# UltraSonic_Anemometer_HW.net
KiCad netlist of a schematic drawn in EasyEDA Pro
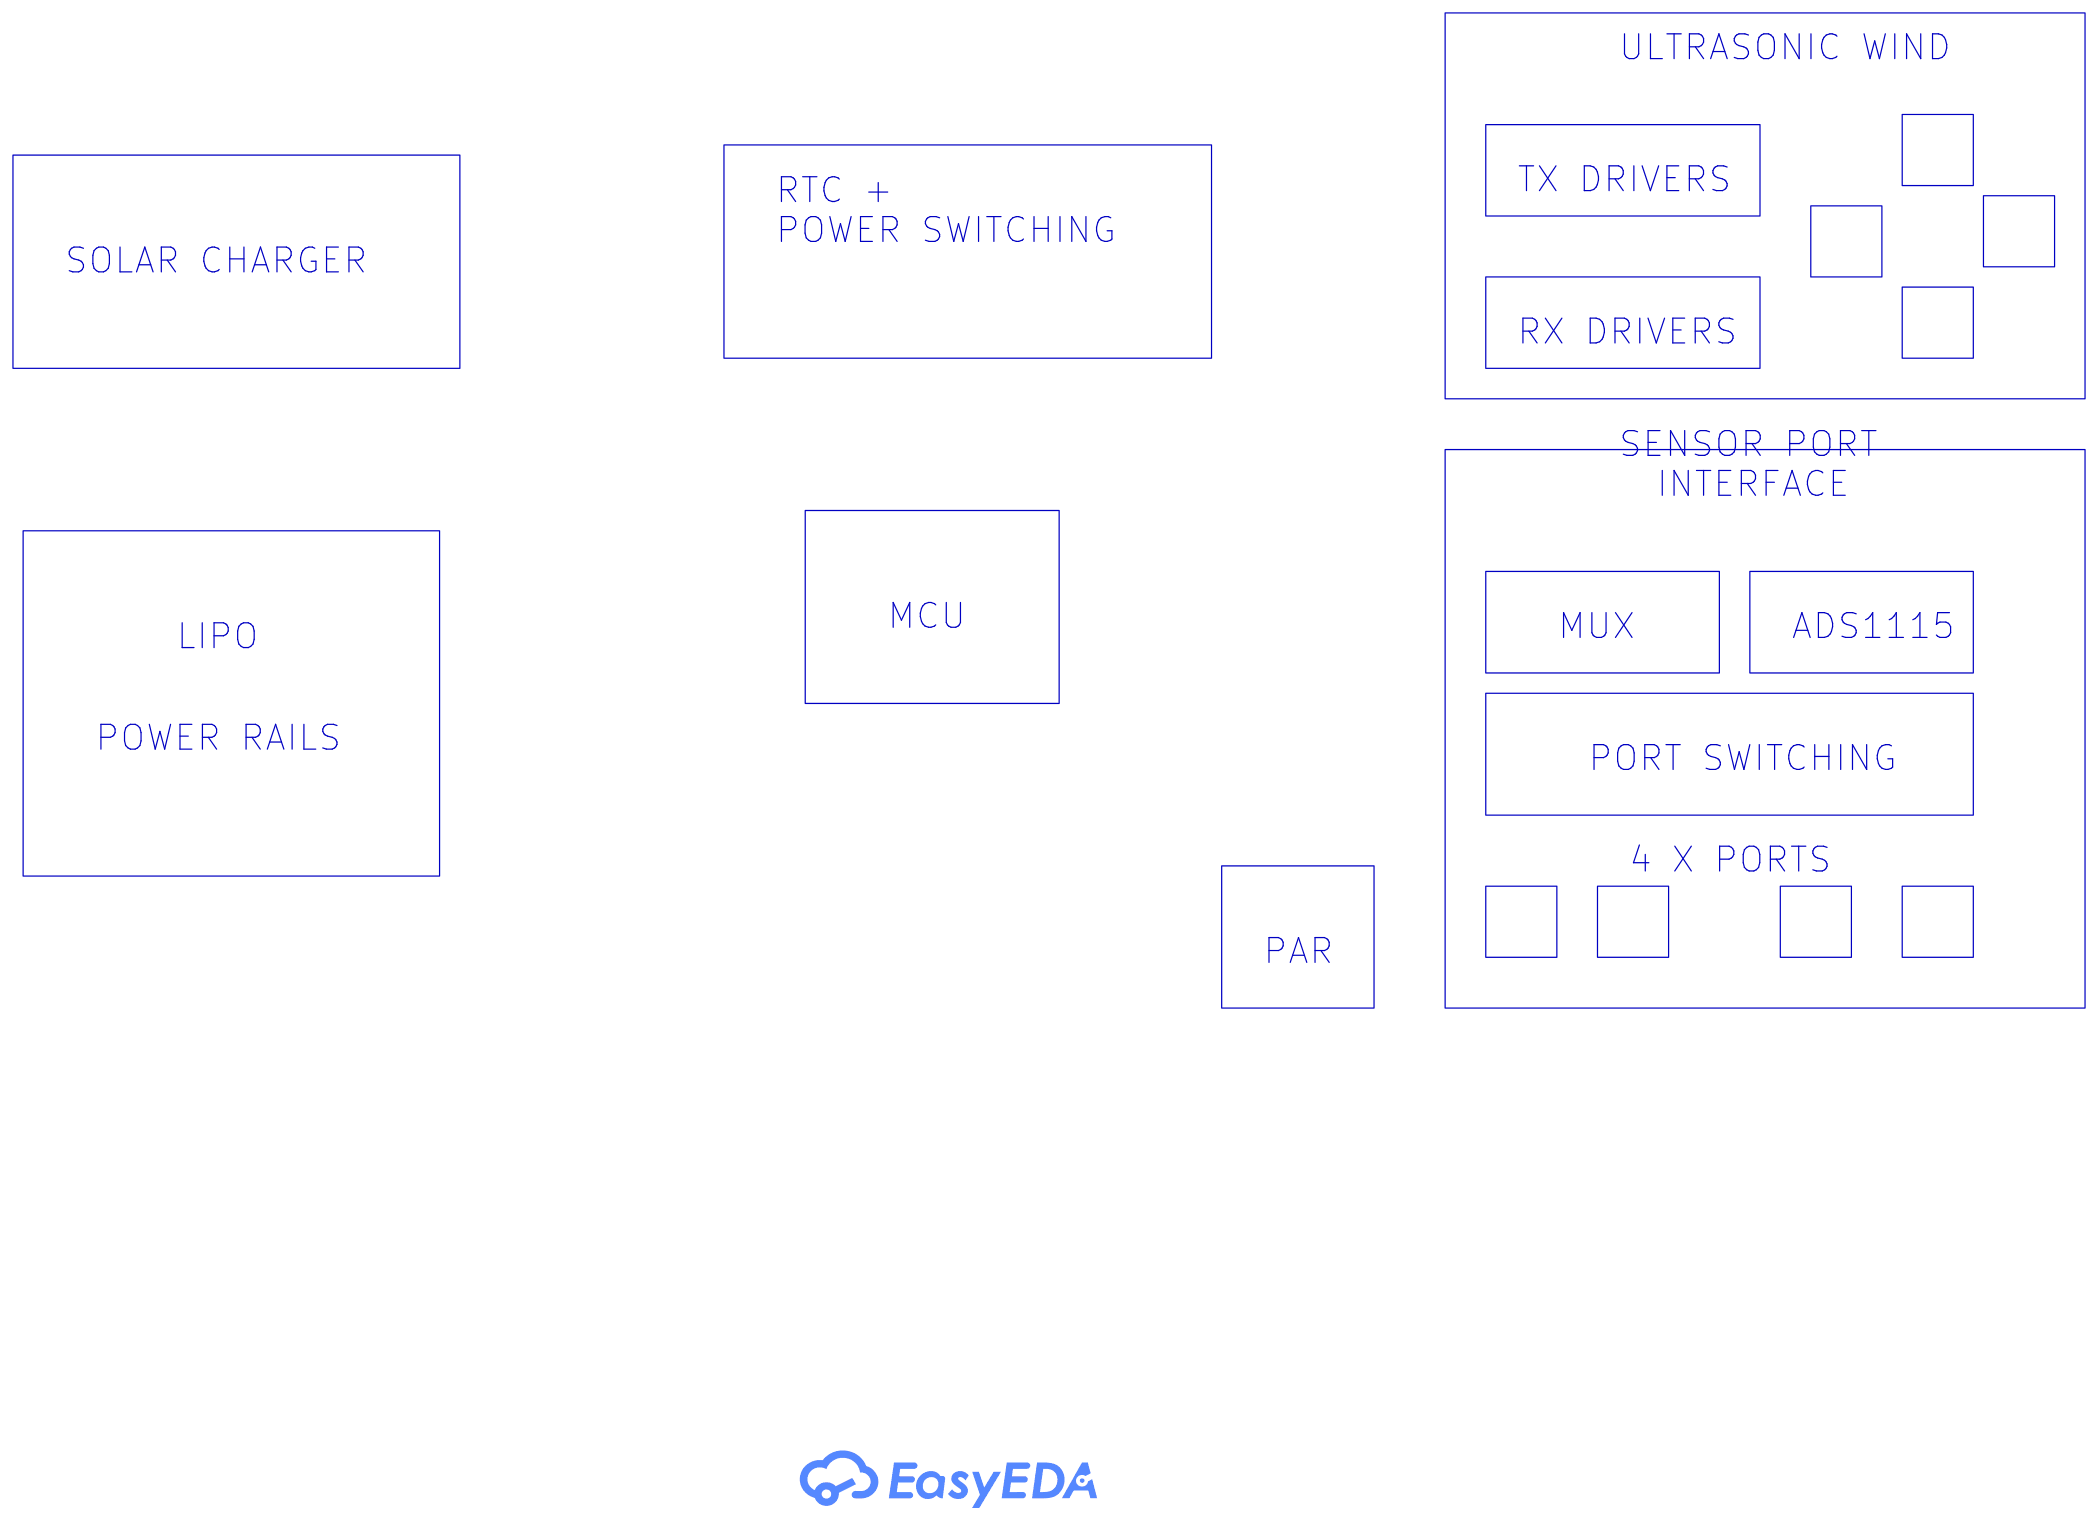
[diagram p0: TOP_LEVEL]
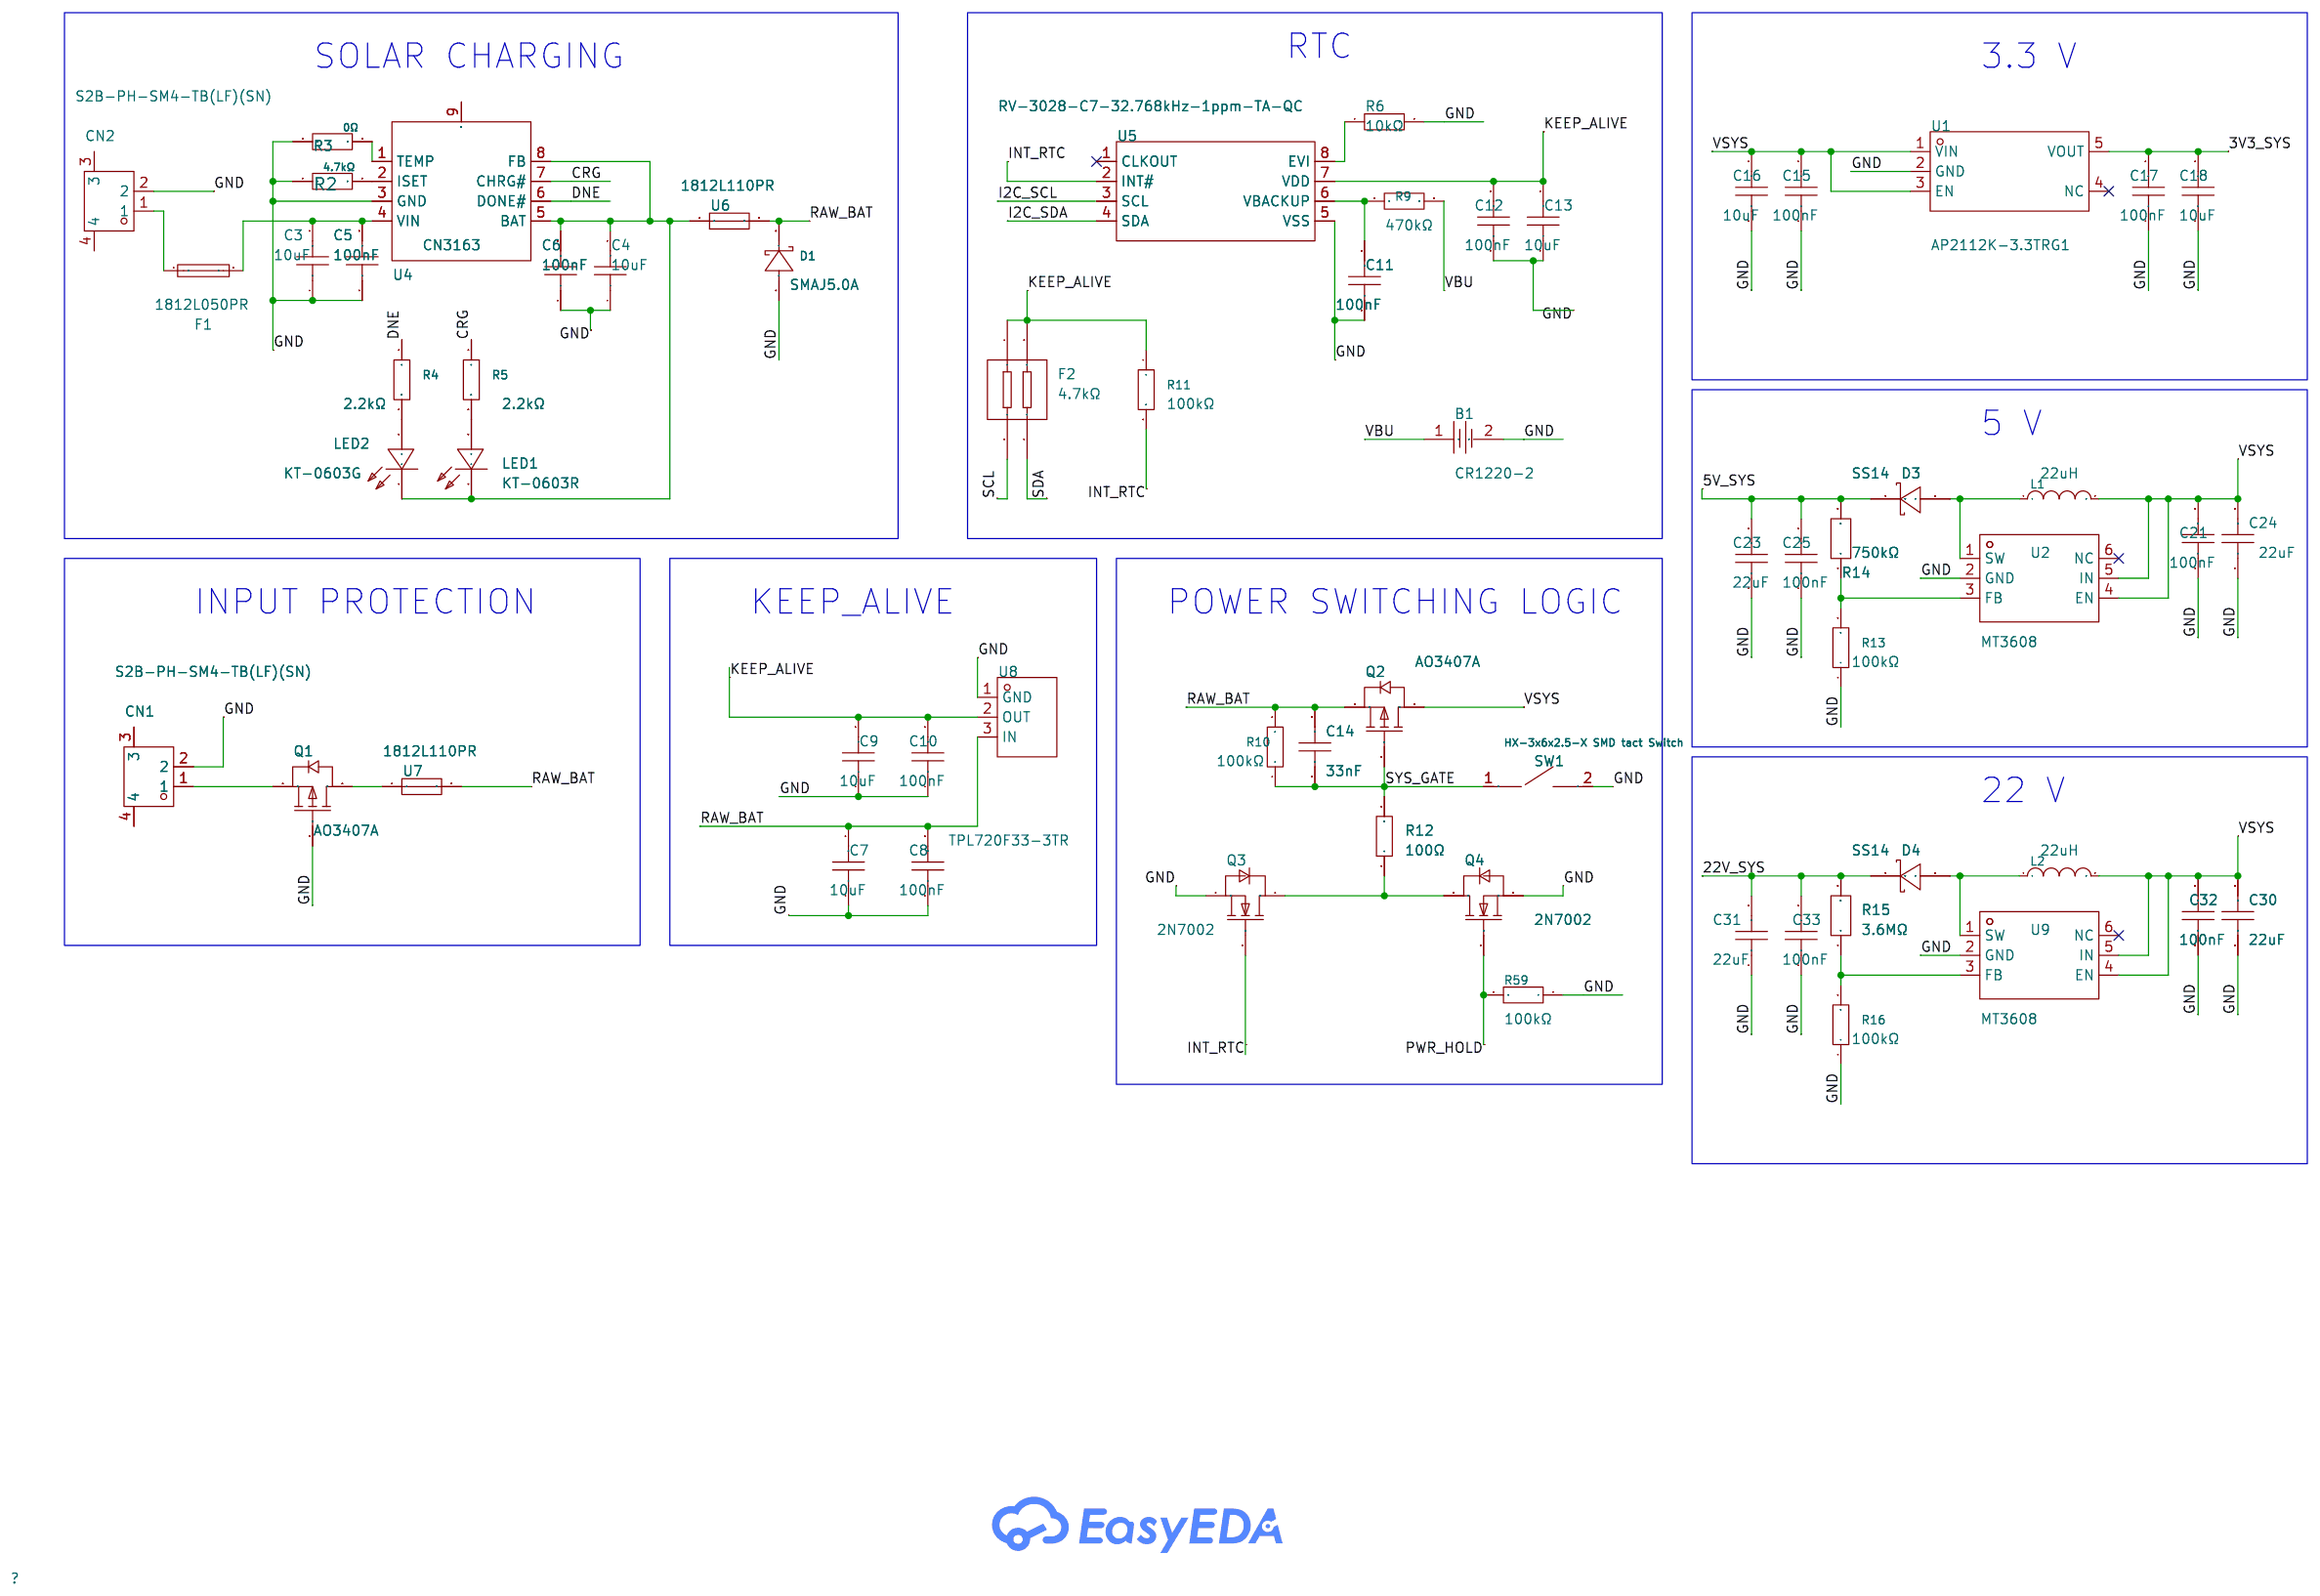
[diagram p1: POWER]
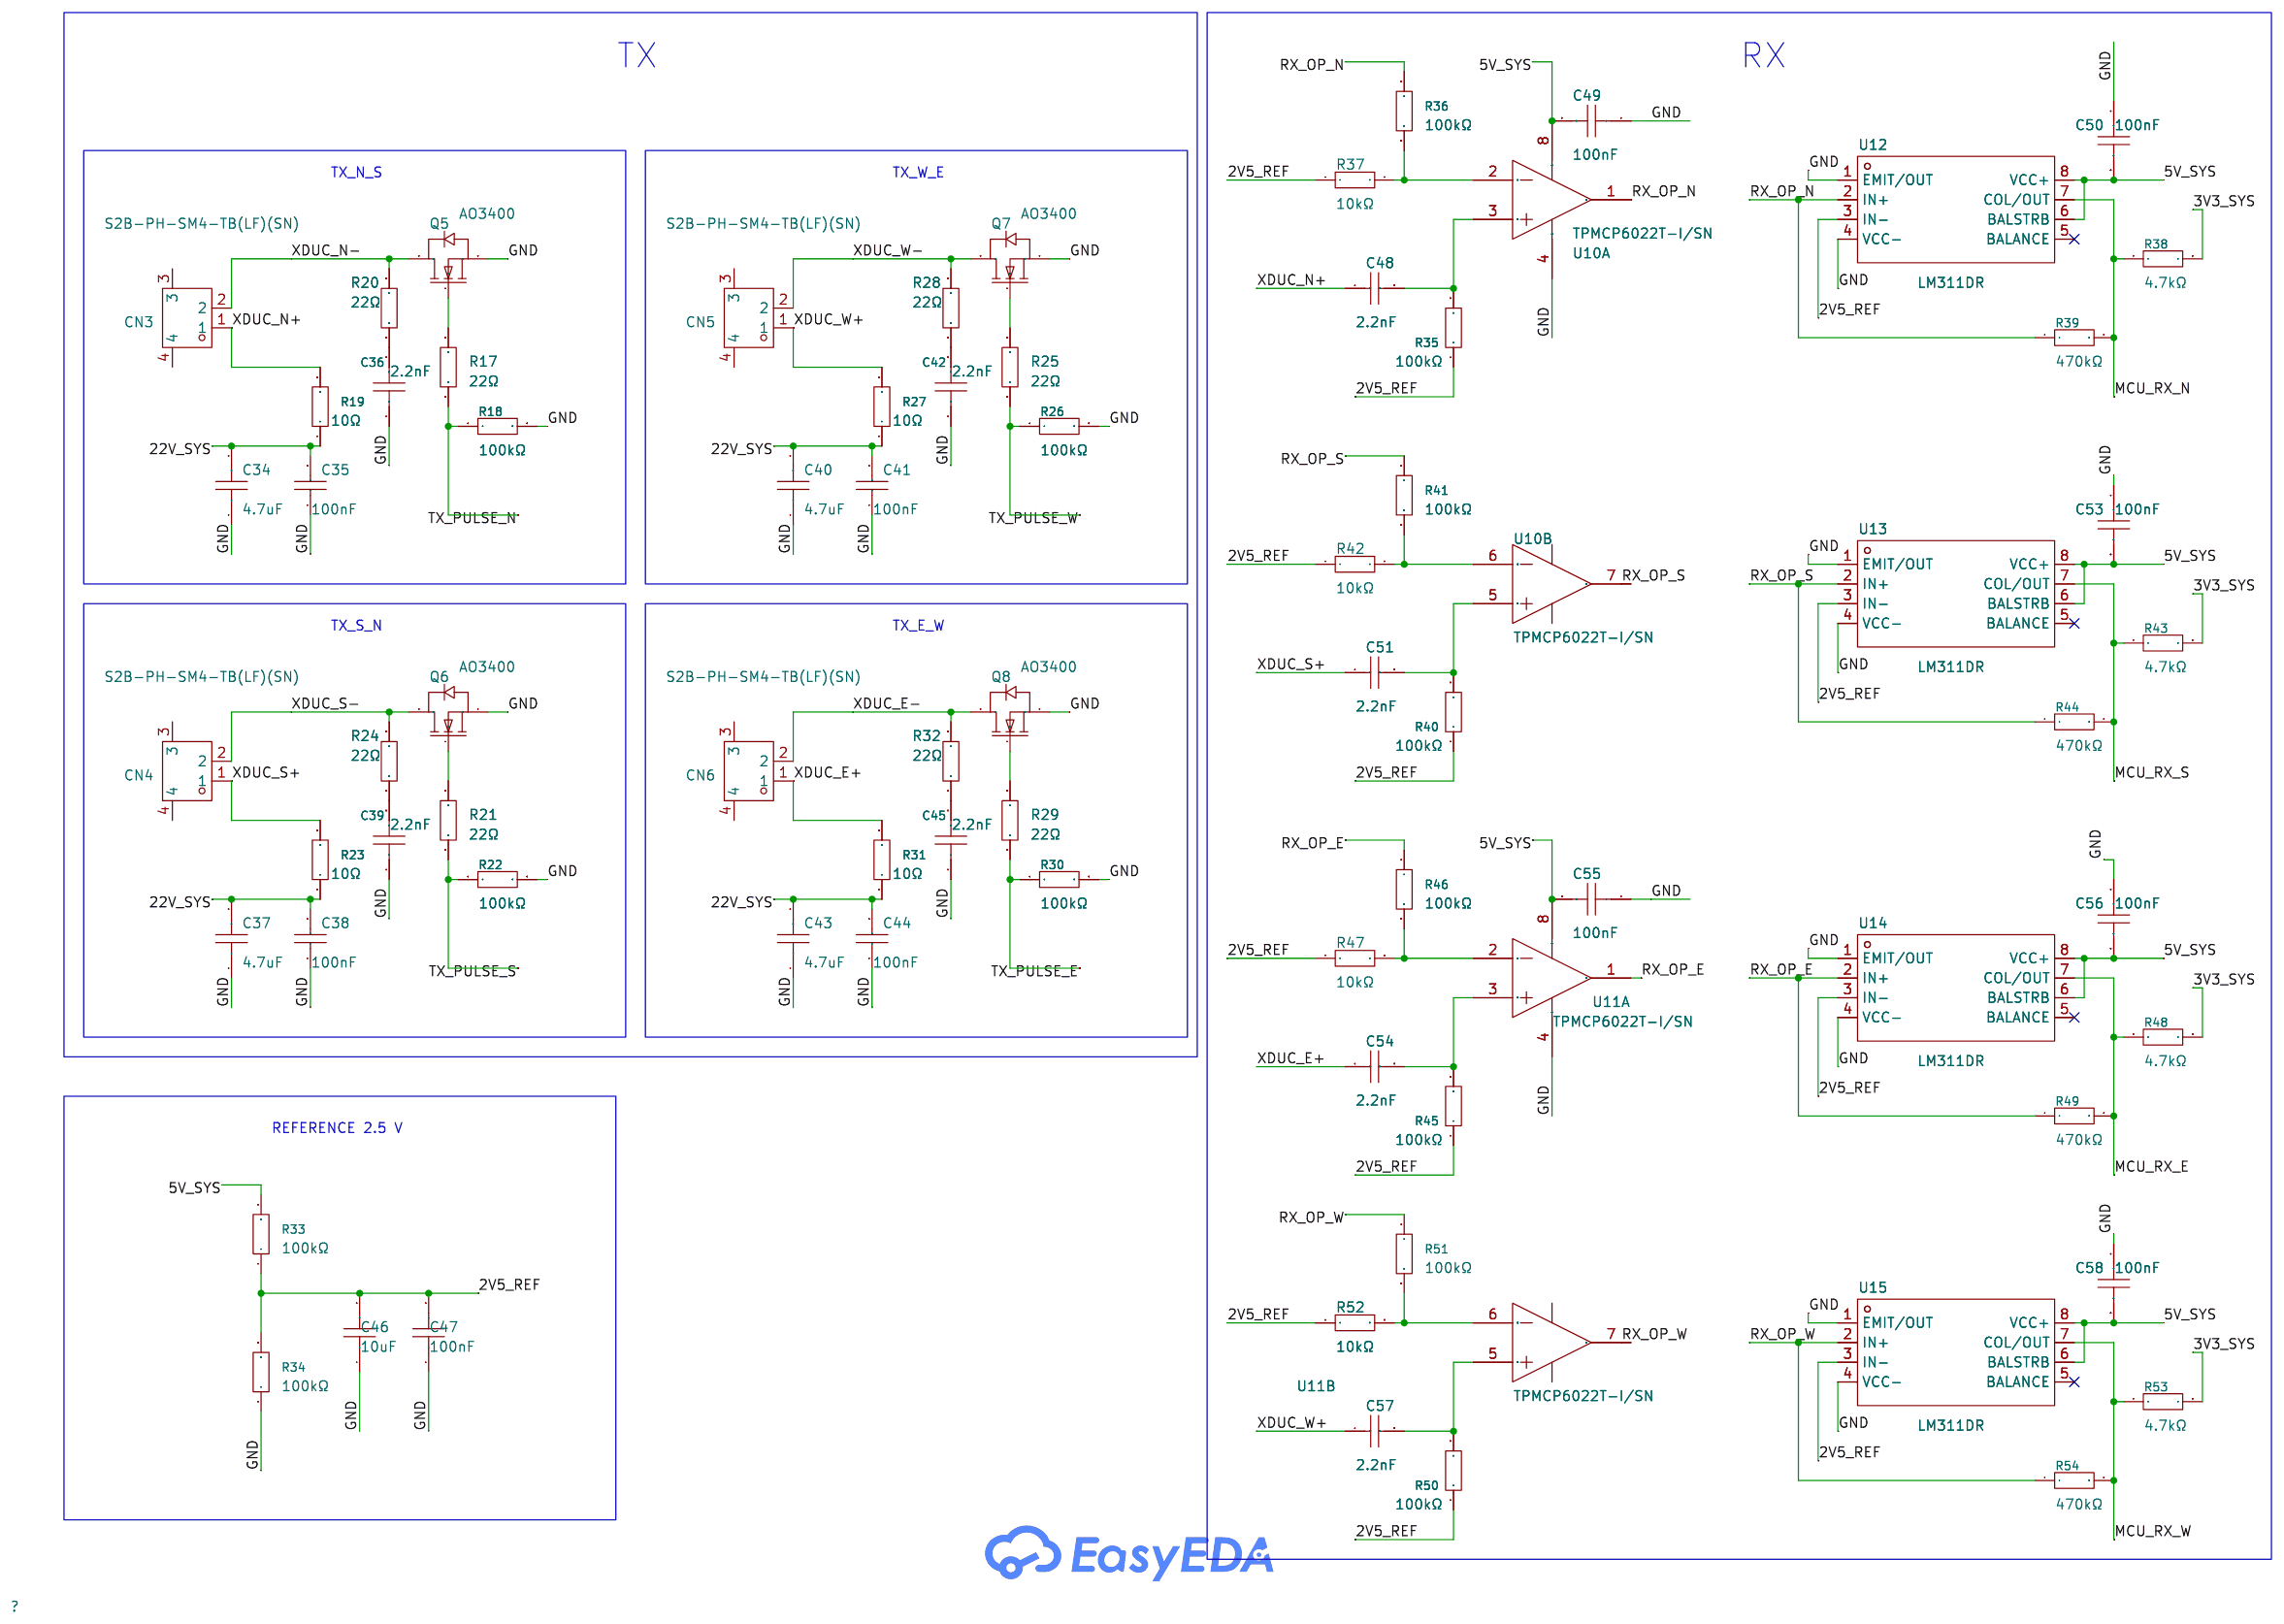
[diagram p2: UlTRASONIC]
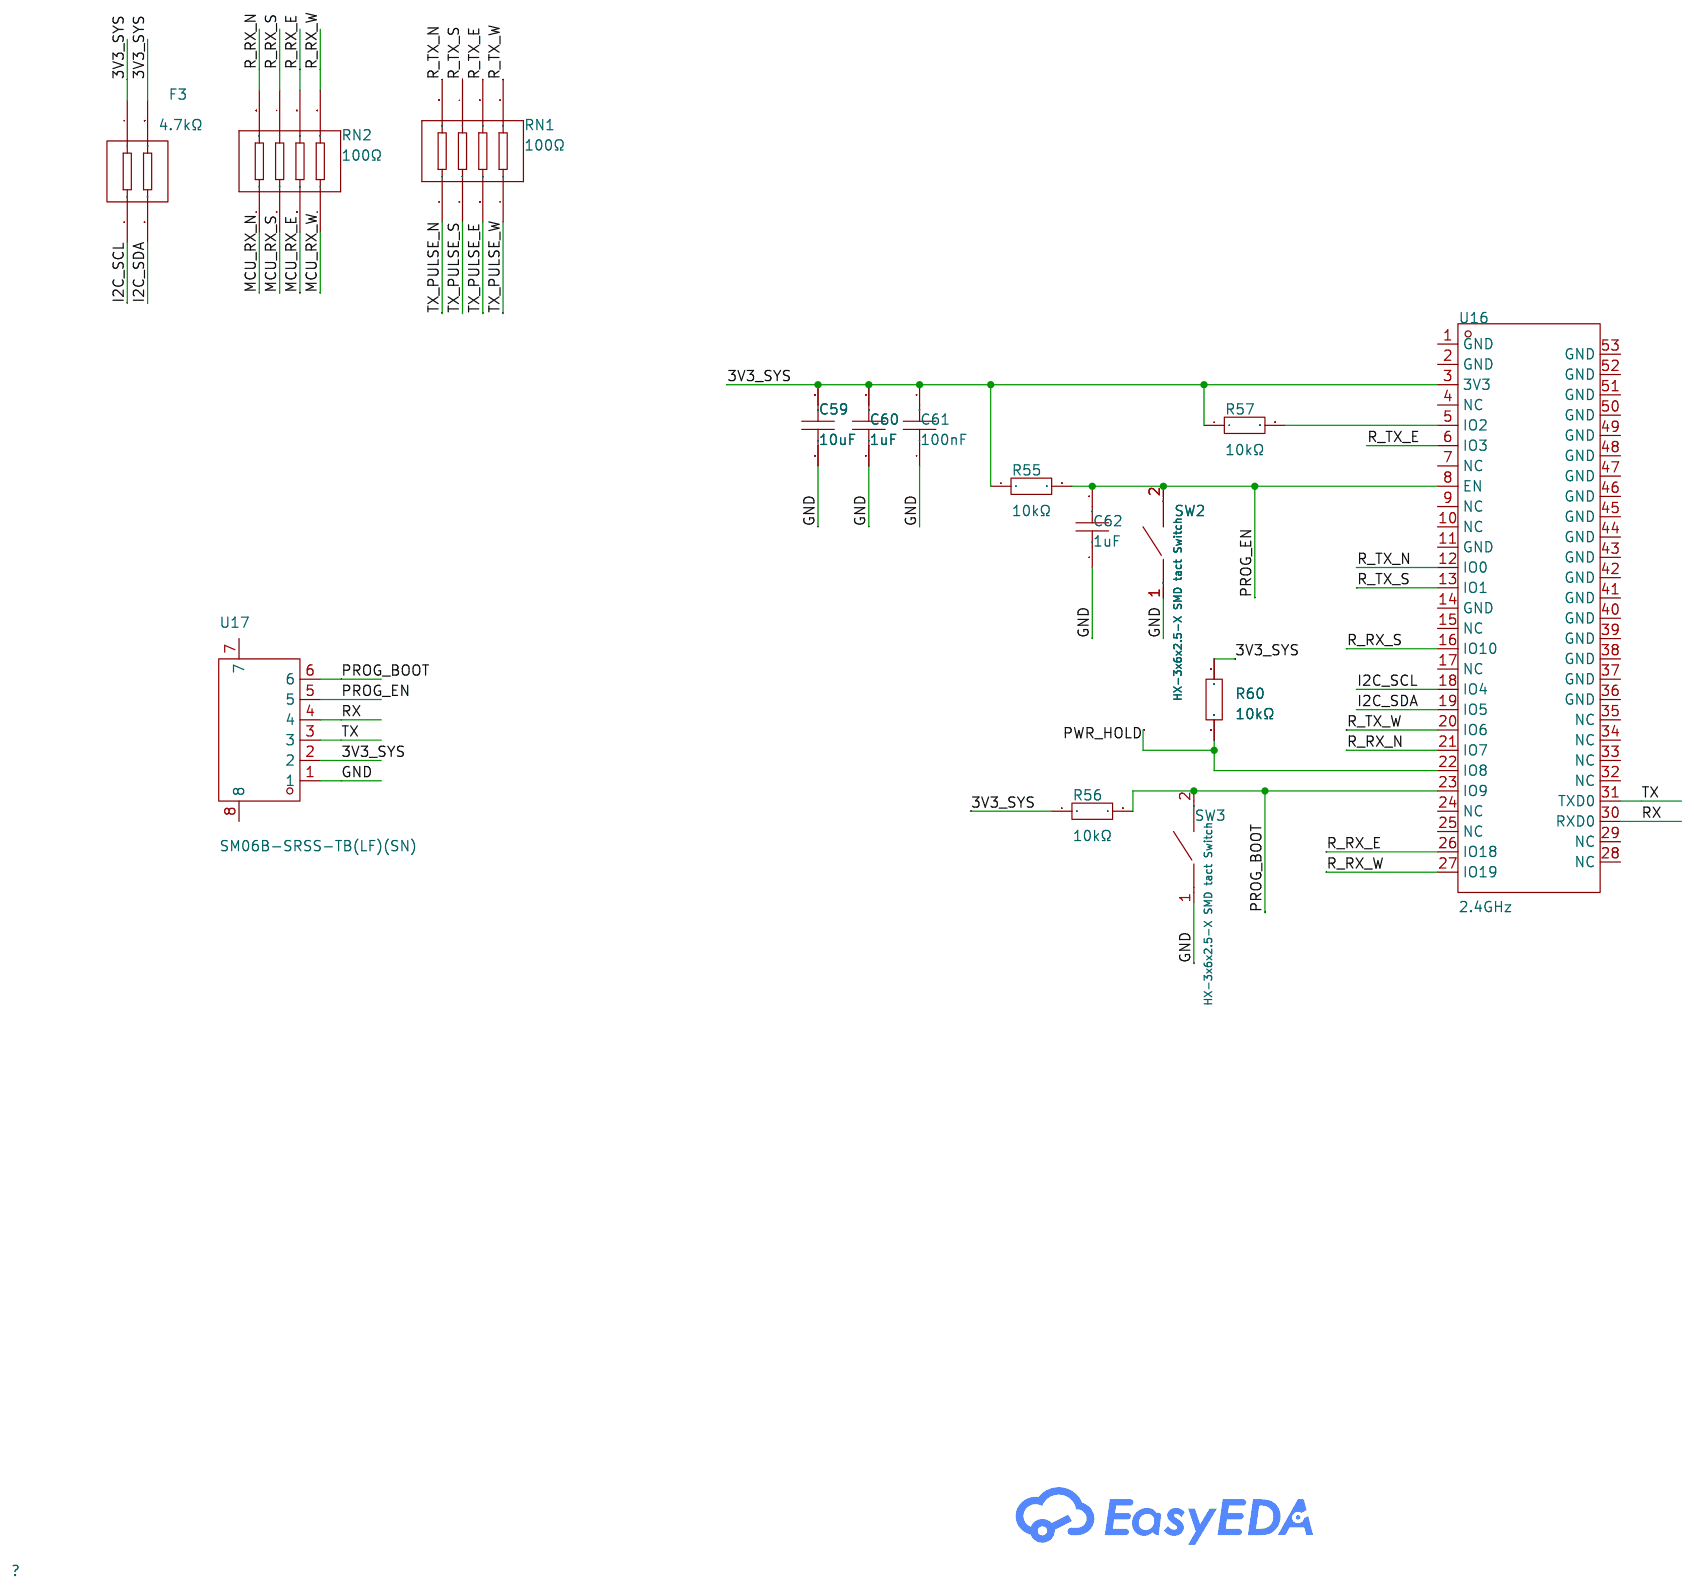
[diagram p3: MCU]
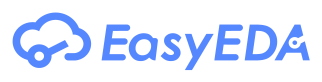
[diagram p4: SENSOR PORTS]

(export (version "E")
  (design (tool "Eeschema 10.0.6"))
  (components
    (comp (ref "B1")
      (value "CR1220-2")
      (footprint "easyedapro:BAT-SMD_CR1220-2")
      (description "Connector Type:Battery Holder Battery Type:CR1220 Operating Temperature:- Operating Temperature:-")
      (fields (field (name "Manufacturer") "QIJEY"))
      (libsource (lib "easyedapro") (part "CR1220-2"))
    )
    (comp (ref "C3")
      (value "10uF")
      (footprint "easyedapro:C0603")
      (fields
        (field (name "Manufacturer Part") "GRM188Z71A106KA73D")
        (field (name "Manufacturer") "muRata(村田)")
      )
      (libsource (lib "easyedapro") (part "GRM188Z71A106KA73D"))
    )
    (comp (ref "C4")
      (value "10uF")
      (footprint "easyedapro:C0603")
      (fields
        (field (name "Manufacturer Part") "GRM188Z71A106KA73D")
        (field (name "Manufacturer") "muRata(村田)")
      )
      (libsource (lib "easyedapro") (part "GRM188Z71A106KA73D"))
    )
    (comp (ref "C5")
      (value "100nF")
      (footprint "easyedapro:C0402")
      (description "Capacitance:100nF Tolerance:±10% Tolerance:±10% Voltage Rating:16V Temperature Coefficient:X7R")
      (fields
        (field (name "Manufacturer Part") "CL05B104KO5NNNC")
        (field (name "Manufacturer") "SAMSUNG(三星)")
      )
      (libsource (lib "easyedapro") (part "CL05B104KO5NNNC"))
    )
    (comp (ref "C6")
      (value "100nF")
      (footprint "easyedapro:C0402")
      (description "Capacitance:100nF Tolerance:±10% Tolerance:±10% Voltage Rating:16V Temperature Coefficient:X7R")
      (fields
        (field (name "Manufacturer Part") "CL05B104KO5NNNC")
        (field (name "Manufacturer") "SAMSUNG(三星)")
      )
      (libsource (lib "easyedapro") (part "CL05B104KO5NNNC"))
    )
    (comp (ref "C7")
      (value "10uF")
      (footprint "easyedapro:C0603")
      (fields
        (field (name "Manufacturer Part") "GRM188Z71A106KA73D")
        (field (name "Manufacturer") "muRata(村田)")
      )
      (libsource (lib "easyedapro") (part "GRM188Z71A106KA73D"))
    )
    (comp (ref "C8")
      (value "100nF")
      (footprint "easyedapro:C0402")
      (description "Capacitance:100nF Tolerance:±10% Tolerance:±10% Voltage Rating:16V Temperature Coefficient:X7R")
      (fields
        (field (name "Manufacturer Part") "CL05B104KO5NNNC")
        (field (name "Manufacturer") "SAMSUNG(三星)")
      )
      (libsource (lib "easyedapro") (part "CL05B104KO5NNNC"))
    )
    (comp (ref "C9")
      (value "10uF")
      (footprint "easyedapro:C0603")
      (fields
        (field (name "Manufacturer Part") "GRM188Z71A106KA73D")
        (field (name "Manufacturer") "muRata(村田)")
      )
      (libsource (lib "easyedapro") (part "GRM188Z71A106KA73D"))
    )
    (comp (ref "C10")
      (value "100nF")
      (footprint "easyedapro:C0402")
      (description "Capacitance:100nF Tolerance:±10% Tolerance:±10% Voltage Rating:16V Temperature Coefficient:X7R")
      (fields
        (field (name "Manufacturer Part") "CL05B104KO5NNNC")
        (field (name "Manufacturer") "SAMSUNG(三星)")
      )
      (libsource (lib "easyedapro") (part "CL05B104KO5NNNC"))
    )
    (comp (ref "C11")
      (value "100nF")
      (footprint "easyedapro:C0402")
      (description "Capacitance:100nF Tolerance:±10% Tolerance:±10% Voltage Rating:16V Temperature Coefficient:X7R")
      (fields
        (field (name "Manufacturer Part") "CL05B104KO5NNNC")
        (field (name "Manufacturer") "SAMSUNG(三星)")
      )
      (libsource (lib "easyedapro") (part "CL05B104KO5NNNC"))
    )
    (comp (ref "C12")
      (value "100nF")
      (footprint "easyedapro:C0402")
      (description "Capacitance:100nF Tolerance:±10% Tolerance:±10% Voltage Rating:16V Temperature Coefficient:X7R")
      (fields
        (field (name "Manufacturer Part") "CL05B104KO5NNNC")
        (field (name "Manufacturer") "SAMSUNG(三星)")
      )
      (libsource (lib "easyedapro") (part "CL05B104KO5NNNC"))
    )
    (comp (ref "C13")
      (value "10uF")
      (footprint "easyedapro:C0603")
      (fields
        (field (name "Manufacturer Part") "GRM188Z71A106KA73D")
        (field (name "Manufacturer") "muRata(村田)")
      )
      (libsource (lib "easyedapro") (part "GRM188Z71A106KA73D"))
    )
    (comp (ref "C14")
      (value "33nF")
      (footprint "easyedapro:C0402")
      (description "Capacitance:33nF Tolerance:±10% Tolerance:±10% Voltage Rating:16V Temperature Coefficient:X7R")
      (fields (field (name "Manufacturer Part") "0402B333K160CT") (field (name "Manufacturer") "Walsin(华新科)"))
      (libsource (lib "easyedapro") (part "0402B333K160CT"))
    )
    (comp (ref "C15")
      (value "100nF")
      (footprint "easyedapro:C0402")
      (description "Capacitance:100nF Tolerance:±10% Tolerance:±10% Voltage Rating:16V Temperature Coefficient:X7R")
      (fields
        (field (name "Manufacturer Part") "CL05B104KO5NNNC")
        (field (name "Manufacturer") "SAMSUNG(三星)")
      )
      (libsource (lib "easyedapro") (part "CL05B104KO5NNNC"))
    )
    (comp (ref "C16")
      (value "10uF")
      (footprint "easyedapro:C0603")
      (fields
        (field (name "Manufacturer Part") "GRM188Z71A106KA73D")
        (field (name "Manufacturer") "muRata(村田)")
      )
      (libsource (lib "easyedapro") (part "GRM188Z71A106KA73D"))
    )
    (comp (ref "C17")
      (value "100nF")
      (footprint "easyedapro:C0402")
      (description "Capacitance:100nF Tolerance:±10% Tolerance:±10% Voltage Rating:16V Temperature Coefficient:X7R")
      (fields
        (field (name "Manufacturer Part") "CL05B104KO5NNNC")
        (field (name "Manufacturer") "SAMSUNG(三星)")
      )
      (libsource (lib "easyedapro") (part "CL05B104KO5NNNC"))
    )
    (comp (ref "C18")
      (value "10uF")
      (footprint "easyedapro:C0603")
      (fields
        (field (name "Manufacturer Part") "GRM188Z71A106KA73D")
        (field (name "Manufacturer") "muRata(村田)")
      )
      (libsource (lib "easyedapro") (part "GRM188Z71A106KA73D"))
    )
    (comp (ref "C21")
      (value "100nF")
      (footprint "easyedapro:C0402")
      (description "Capacitance:100nF Tolerance:±10% Tolerance:±10% Voltage Rating:16V Temperature Coefficient:X7R")
      (fields
        (field (name "Manufacturer Part") "CL05B104KO5NNNC")
        (field (name "Manufacturer") "SAMSUNG(三星)")
      )
      (libsource (lib "easyedapro") (part "CL05B104KO5NNNC"))
    )
    (comp (ref "C23")
      (value "22uF")
      (footprint "easyedapro:C0603")
      (description "Capacitance:22uF Tolerance:±20% Tolerance:±20% Voltage Rating:10V Temperature Coefficient:X5R")
      (fields
        (field (name "Manufacturer Part") "CL10A226MP8NUNE")
        (field (name "Manufacturer") "SAMSUNG(三星)")
      )
      (libsource (lib "easyedapro") (part "CL10A226MP8NUNE"))
    )
    (comp (ref "C24")
      (value "22uF")
      (footprint "easyedapro:C0603")
      (description "Capacitance:22uF Tolerance:±20% Tolerance:±20% Voltage Rating:10V Temperature Coefficient:X5R")
      (fields
        (field (name "Manufacturer Part") "CL10A226MP8NUNE")
        (field (name "Manufacturer") "SAMSUNG(三星)")
      )
      (libsource (lib "easyedapro") (part "CL10A226MP8NUNE"))
    )
    (comp (ref "C25")
      (value "100nF")
      (footprint "easyedapro:C0402")
      (description "Capacitance:100nF Tolerance:±10% Tolerance:±10% Voltage Rating:16V Temperature Coefficient:X7R")
      (fields
        (field (name "Manufacturer Part") "CL05B104KO5NNNC")
        (field (name "Manufacturer") "SAMSUNG(三星)")
      )
      (libsource (lib "easyedapro") (part "CL05B104KO5NNNC"))
    )
    (comp (ref "C30")
      (value "22uF")
      (footprint "easyedapro:C1210")
      (description "Capacitance:22uF Tolerance:±10% Tolerance:±10% Voltage Rating:25V Temperature Coefficient:X7R")
      (fields
        (field (name "Manufacturer Part") "CL32B226KAJNNNE")
        (field (name "Manufacturer") "SAMSUNG(三星)")
      )
      (libsource (lib "easyedapro") (part "CL32B226KAJNNNE"))
    )
    (comp (ref "C31")
      (value "22uF")
      (footprint "easyedapro:C1210")
      (description "Capacitance:22uF Tolerance:±10% Tolerance:±10% Voltage Rating:25V Temperature Coefficient:X7R")
      (fields
        (field (name "Manufacturer Part") "CL32B226KAJNNNE")
        (field (name "Manufacturer") "SAMSUNG(三星)")
      )
      (libsource (lib "easyedapro") (part "CL32B226KAJNNNE"))
    )
    (comp (ref "C32")
      (value "100nF")
      (footprint "easyedapro:C0402")
      (description "Capacitance:100nF Tolerance:±10% Tolerance:±10% Voltage Rating:25V Temperature Coefficient:X7R")
      (fields
        (field (name "Manufacturer Part") "CGA0402X7R104K250GT")
        (field (name "Manufacturer") "HRE(芯声)")
      )
      (libsource (lib "easyedapro") (part "CGA0402X7R104K250GT"))
    )
    (comp (ref "C33")
      (value "100nF")
      (footprint "easyedapro:C0402")
      (description "Capacitance:100nF Tolerance:±10% Tolerance:±10% Voltage Rating:25V Temperature Coefficient:X7R")
      (fields
        (field (name "Manufacturer Part") "CGA0402X7R104K250GT")
        (field (name "Manufacturer") "HRE(芯声)")
      )
      (libsource (lib "easyedapro") (part "CGA0402X7R104K250GT"))
    )
    (comp (ref "CN1")
      (value "S2B-PH-SM4-TB(LF)(SN)")
      (footprint "easyedapro:CONN-SMD_P2.00_S2B-PH-SM4-TB-LF-SN")
      (fields (field (name "Manufacturer") "JST"))
      (libsource (lib "easyedapro") (part "S2B-PH-SM4-TB(LF)(SN)"))
    )
    (comp (ref "CN2")
      (value "S2B-PH-SM4-TB(LF)(SN)")
      (footprint "easyedapro:CONN-SMD_P2.00_S2B-PH-SM4-TB-LF-SN")
      (fields (field (name "Manufacturer") "JST"))
      (libsource (lib "easyedapro") (part "S2B-PH-SM4-TB(LF)(SN)"))
    )
    (comp (ref "D1")
      (value "SMAJ5.0A")
      (footprint "easyedapro:SMA_L4.4-W2.6-LS5.0-R-RD")
      (fields (field (name "Manufacturer") "SHIKUES(时科)"))
      (libsource (lib "easyedapro") (part "SMAJ5.0A_C499811"))
    )
    (comp (ref "D3")
      (value "SS14")
      (footprint "easyedapro:SMA_L4.4-W2.6-LS5.0-RD")
      (fields (field (name "Manufacturer") "HT(金誉)"))
      (libsource (lib "easyedapro") (part "SS14_C48782961"))
    )
    (comp (ref "D4")
      (value "SS14")
      (footprint "easyedapro:SMA_L4.4-W2.6-LS5.0-RD")
      (fields (field (name "Manufacturer") "HT(金誉)"))
      (libsource (lib "easyedapro") (part "SS14_C48782961"))
    )
    (comp (ref "F1")
      (value "1812L050PR")
      (footprint "easyedapro:F1812")
      (fields (field (name "Manufacturer") "Littelfuse(美国力特)"))
      (libsource (lib "easyedapro") (part "1812L050PR"))
    )
    (comp (ref "F2")
      (value "4.7kΩ")
      (footprint "easyedapro:RES-ARRAY-SMD_0404-4P-L1.0-W1.0-BL")
      (fields (field (name "Manufacturer Part") "YC122-JR-074K7L") (field (name "Manufacturer") "YAGEO(国巨)"))
      (libsource (lib "easyedapro") (part "YC122-JR-074K7L"))
    )
    (comp (ref "L1")
      (value "22uH")
      (footprint "easyedapro:IND-SMD_L4.6-W4.2_SMMS0420")
      (fields (field (name "Manufacturer Part") "SMMS0420-220M") (field (name "Manufacturer") "SXN(顺翔诺)"))
      (libsource (lib "easyedapro") (part "SMMS0420-220M"))
    )
    (comp (ref "L2")
      (value "22uH")
      (footprint "easyedapro:IND-SMD_L4.6-W4.2_SMMS0420")
      (fields (field (name "Manufacturer Part") "SMMS0420-220M") (field (name "Manufacturer") "SXN(顺翔诺)"))
      (libsource (lib "easyedapro") (part "SMMS0420-220M"))
    )
    (comp (ref "LED1")
      (value "KT-0603R")
      (footprint "easyedapro:LED0603-RD")
      (fields (field (name "Manufacturer") "KENTO"))
      (libsource (lib "easyedapro") (part "KT-0603R"))
    )
    (comp (ref "LED2")
      (value "KT-0603G")
      (footprint "easyedapro:LED0603-RD")
      (fields (field (name "Manufacturer") "KENTO"))
      (libsource (lib "easyedapro") (part "0603 Green 509-620mcd"))
    )
    (comp (ref "Q1")
      (value "AO3407A")
      (footprint "easyedapro:SOT-23-3_L2.9-W1.6-P1.90-LS2.8-BR")
      (fields (field (name "Manufacturer") "AOS"))
      (libsource (lib "easyedapro") (part "AO3407A"))
    )
    (comp (ref "Q2")
      (value "AO3407A")
      (footprint "easyedapro:SOT-23-3_L2.9-W1.6-P1.90-LS2.8-BR")
      (fields (field (name "Manufacturer") "AOS"))
      (libsource (lib "easyedapro") (part "AO3407A"))
    )
    (comp (ref "Q3")
      (value "2N7002")
      (footprint "easyedapro:SOT-23-3_L2.9-W1.3-P1.90-LS2.4-BR")
      (fields (field (name "Manufacturer") "CBI(创基)"))
      (libsource (lib "easyedapro") (part "2N7002_C51315010"))
    )
    (comp (ref "Q4")
      (value "2N7002")
      (footprint "easyedapro:SOT-23-3_L2.9-W1.3-P1.90-LS2.4-BR")
      (fields (field (name "Manufacturer") "CBI(创基)"))
      (libsource (lib "easyedapro") (part "2N7002_C51315010"))
    )
    (comp (ref "R2")
      (value "4.7kΩ")
      (footprint "easyedapro:R0402")
      (fields
        (field (name "Manufacturer Part") "0402WGF4701TCE")
        (field (name "Manufacturer") "UNI-ROYAL(厚声)")
      )
      (libsource (lib "easyedapro") (part "0402WGF4701TCE"))
    )
    (comp (ref "R3")
      (value "0Ω")
      (footprint "easyedapro:R0603")
      (fields
        (field (name "Manufacturer Part") "0603WAF0000T5E")
        (field (name "Manufacturer") "UNI-ROYAL(厚声)")
      )
      (libsource (lib "easyedapro") (part "0603WAF0000T5E"))
    )
    (comp (ref "R4")
      (value "2.2kΩ")
      (footprint "easyedapro:R0402")
      (fields
        (field (name "Manufacturer Part") "0402WGF2201TCE")
        (field (name "Manufacturer") "UNI-ROYAL(厚声)")
      )
      (libsource (lib "easyedapro") (part "0402WGF2201TCE"))
    )
    (comp (ref "R5")
      (value "2.2kΩ")
      (footprint "easyedapro:R0402")
      (fields
        (field (name "Manufacturer Part") "0402WGF2201TCE")
        (field (name "Manufacturer") "UNI-ROYAL(厚声)")
      )
      (libsource (lib "easyedapro") (part "0402WGF2201TCE"))
    )
    (comp (ref "R6")
      (value "10kΩ")
      (footprint "easyedapro:R0402")
      (fields
        (field (name "Manufacturer Part") "0402WGF1002TCE")
        (field (name "Manufacturer") "UNI-ROYAL(厚声)")
      )
      (libsource (lib "easyedapro") (part "0402WGF1002TCE"))
    )
    (comp (ref "R9")
      (value "470kΩ")
      (footprint "easyedapro:R0603")
      (fields
        (field (name "Manufacturer Part") "0603WAF4703T5E")
        (field (name "Manufacturer") "UNI-ROYAL(厚声)")
      )
      (libsource (lib "easyedapro") (part "0603WAF4703T5E"))
    )
    (comp (ref "R10")
      (value "100kΩ")
      (footprint "easyedapro:R0402")
      (fields
        (field (name "Manufacturer Part") "0402WGF1003TCE")
        (field (name "Manufacturer") "UNI-ROYAL(厚声)")
      )
      (libsource (lib "easyedapro") (part "0402WGF1003TCE"))
    )
    (comp (ref "R11")
      (value "100kΩ")
      (footprint "easyedapro:R0402")
      (fields
        (field (name "Manufacturer Part") "0402WGF1003TCE")
        (field (name "Manufacturer") "UNI-ROYAL(厚声)")
      )
      (libsource (lib "easyedapro") (part "0402WGF1003TCE"))
    )
    (comp (ref "R12")
      (value "100Ω")
      (footprint "easyedapro:R0402")
      (fields
        (field (name "Manufacturer Part") "0402WGF1000TCE")
        (field (name "Manufacturer") "UNI-ROYAL(厚声)")
      )
      (libsource (lib "easyedapro") (part "0402WGF1000TCE"))
    )
    (comp (ref "R13")
      (value "100kΩ")
      (footprint "easyedapro:R0402")
      (fields
        (field (name "Manufacturer Part") "0402WGF1003TCE")
        (field (name "Manufacturer") "UNI-ROYAL(厚声)")
      )
      (libsource (lib "easyedapro") (part "0402WGF1003TCE"))
    )
    (comp (ref "R14")
      (value "750kΩ")
      (footprint "easyedapro:R0402")
      (fields (field (name "Manufacturer Part") "FRC0402F7503TS") (field (name "Manufacturer") "FOJAN(富捷)"))
      (libsource (lib "easyedapro") (part "FRC0402F7503TS"))
    )
    (comp (ref "R15")
      (value "3.6MΩ")
      (footprint "easyedapro:R0402")
      (fields (field (name "Manufacturer Part") "AC0402JR-073M6L") (field (name "Manufacturer") "YAGEO(国巨)"))
      (libsource (lib "easyedapro") (part "AC0402JR-073M6L"))
    )
    (comp (ref "R16")
      (value "100kΩ")
      (footprint "easyedapro:R0402")
      (fields
        (field (name "Manufacturer Part") "0402WGF1003TCE")
        (field (name "Manufacturer") "UNI-ROYAL(厚声)")
      )
      (libsource (lib "easyedapro") (part "0402WGF1003TCE"))
    )
    (comp (ref "R59")
      (value "100kΩ")
      (footprint "easyedapro:R0402")
      (fields
        (field (name "Manufacturer Part") "0402WGF1003TCE")
        (field (name "Manufacturer") "UNI-ROYAL(厚声)")
      )
      (libsource (lib "easyedapro") (part "0402WGF1003TCE"))
    )
    (comp (ref "SW1")
      (value "HX-3x6x2.5-X SMD tact Switch")
      (footprint "easyedapro:SW-SMD_HX-3X6X2.5-X")
      (fields (field (name "Manufacturer") "hanxia(韩下)"))
      (libsource (lib "easyedapro") (part "HX-3X6X2.5-X SMD TACT SWITCH"))
    )
    (comp (ref "U1")
      (value "AP2112K-3.3TRG1")
      (footprint "easyedapro:SOT-25-5_L2.9-W1.6-P0.95-LS2.8-BL")
      (fields (field (name "Manufacturer") "DIODES(美台)"))
      (libsource (lib "easyedapro") (part "AP2112K-3.3TRG1"))
    )
    (comp (ref "U2")
      (value "MT3608")
      (footprint "easyedapro:SOT-23-6_L2.9-W1.6-P0.95-LS2.8-BL")
      (fields (field (name "Manufacturer") "西安航天民芯"))
      (libsource (lib "easyedapro") (part "MT3608"))
    )
    (comp (ref "U4")
      (value "CN3163")
      (footprint "easyedapro:ESOP-8_L4.9-W3.9-P1.27-LS6.0-BL-EP")
      (fields (field (name "Manufacturer") "CONSONANCE(上海如韵)"))
      (libsource (lib "easyedapro") (part "CN3163"))
    )
    (comp (ref "U5")
      (value "RV-3028-C7-32.768kHz-1ppm-TA-QC")
      (footprint "easyedapro:OSC-SMD_8P-L3.2-W1.5-P0.90-BL")
      (description "Voltage - Supply:1.1V~5.5V Voltage - Supply:1.1V~5.5V")
      (fields (field (name "Manufacturer") "Micro Crystal(瑞士微晶)"))
      (libsource (lib "easyedapro") (part "RV-3028-C7 32.768KHZ 1PPM TA QC"))
    )
    (comp (ref "U6")
      (value "1812L110PR")
      (footprint "easyedapro:FUSE-SMD_L4.7-W3.4")
      (fields (field (name "Manufacturer") "Littelfuse(美国力特)"))
      (libsource (lib "easyedapro") (part "1812L110PR"))
    )
    (comp (ref "U7")
      (value "1812L110PR")
      (footprint "easyedapro:FUSE-SMD_L4.7-W3.4")
      (fields (field (name "Manufacturer") "Littelfuse(美国力特)"))
      (libsource (lib "easyedapro") (part "1812L110PR"))
    )
    (comp (ref "U8")
      (value "TPL720F33-3TR")
      (footprint "easyedapro:SOT-23-3_L2.9-W1.6-P1.90-LS2.8-BR")
      (fields (field (name "Manufacturer") "3PEAK(思瑞浦)"))
      (libsource (lib "easyedapro") (part "TPL720F33-3TR"))
    )
    (comp (ref "U9")
      (value "MT3608")
      (footprint "easyedapro:SOT-23-6_L2.9-W1.6-P0.95-LS2.8-BL")
      (fields (field (name "Manufacturer") "西安航天民芯"))
      (libsource (lib "easyedapro") (part "MT3608"))
    )
    (comp (ref "C34")
      (value "4.7uF")
      (footprint "easyedapro:C0603")
      (description "Capacitance:4.7uF Tolerance:±10% Tolerance:±10% Voltage Rating:25V Temperature Coefficient:X5R")
      (fields
        (field (name "Manufacturer Part") "CGA0603X5R475K250JT")
        (field (name "Manufacturer") "HRE(芯声)")
      )
      (libsource (lib "easyedapro") (part "CGA0603X5R475K250JT"))
    )
    (comp (ref "C35")
      (value "100nF")
      (footprint "easyedapro:C0402")
      (description "Capacitance:100nF Tolerance:±10% Tolerance:±10% Voltage Rating:25V Temperature Coefficient:X5R")
      (fields
        (field (name "Manufacturer Part") "CL05A104KA5NNNC")
        (field (name "Manufacturer") "SAMSUNG(三星)")
      )
      (libsource (lib "easyedapro") (part "CL05A104KA5NNNC"))
    )
    (comp (ref "C36")
      (value "2.2nF")
      (footprint "easyedapro:C0402")
      (fields
        (field (name "Manufacturer Part") "CC0402KRX7R8BB222")
        (field (name "Manufacturer") "YAGEO(国巨)")
      )
      (libsource (lib "easyedapro") (part "CC0402KRX7R8BB222"))
    )
    (comp (ref "C37")
      (value "4.7uF")
      (footprint "easyedapro:C0603")
      (description "Capacitance:4.7uF Tolerance:±10% Tolerance:±10% Voltage Rating:25V Temperature Coefficient:X5R")
      (fields
        (field (name "Manufacturer Part") "CGA0603X5R475K250JT")
        (field (name "Manufacturer") "HRE(芯声)")
      )
      (libsource (lib "easyedapro") (part "CGA0603X5R475K250JT"))
    )
    (comp (ref "C38")
      (value "100nF")
      (footprint "easyedapro:C0402")
      (description "Capacitance:100nF Tolerance:±10% Tolerance:±10% Voltage Rating:25V Temperature Coefficient:X5R")
      (fields
        (field (name "Manufacturer Part") "CL05A104KA5NNNC")
        (field (name "Manufacturer") "SAMSUNG(三星)")
      )
      (libsource (lib "easyedapro") (part "CL05A104KA5NNNC"))
    )
    (comp (ref "C39")
      (value "2.2nF")
      (footprint "easyedapro:C0402")
      (fields
        (field (name "Manufacturer Part") "CC0402KRX7R8BB222")
        (field (name "Manufacturer") "YAGEO(国巨)")
      )
      (libsource (lib "easyedapro") (part "CC0402KRX7R8BB222"))
    )
    (comp (ref "C40")
      (value "4.7uF")
      (footprint "easyedapro:C0603")
      (description "Capacitance:4.7uF Tolerance:±10% Tolerance:±10% Voltage Rating:25V Temperature Coefficient:X5R")
      (fields
        (field (name "Manufacturer Part") "CGA0603X5R475K250JT")
        (field (name "Manufacturer") "HRE(芯声)")
      )
      (libsource (lib "easyedapro") (part "CGA0603X5R475K250JT"))
    )
    (comp (ref "C41")
      (value "100nF")
      (footprint "easyedapro:C0402")
      (description "Capacitance:100nF Tolerance:±10% Tolerance:±10% Voltage Rating:25V Temperature Coefficient:X5R")
      (fields
        (field (name "Manufacturer Part") "CL05A104KA5NNNC")
        (field (name "Manufacturer") "SAMSUNG(三星)")
      )
      (libsource (lib "easyedapro") (part "CL05A104KA5NNNC"))
    )
    (comp (ref "C42")
      (value "2.2nF")
      (footprint "easyedapro:C0402")
      (fields
        (field (name "Manufacturer Part") "CC0402KRX7R8BB222")
        (field (name "Manufacturer") "YAGEO(国巨)")
      )
      (libsource (lib "easyedapro") (part "CC0402KRX7R8BB222"))
    )
    (comp (ref "C43")
      (value "4.7uF")
      (footprint "easyedapro:C0603")
      (description "Capacitance:4.7uF Tolerance:±10% Tolerance:±10% Voltage Rating:25V Temperature Coefficient:X5R")
      (fields
        (field (name "Manufacturer Part") "CGA0603X5R475K250JT")
        (field (name "Manufacturer") "HRE(芯声)")
      )
      (libsource (lib "easyedapro") (part "CGA0603X5R475K250JT"))
    )
    (comp (ref "C44")
      (value "100nF")
      (footprint "easyedapro:C0402")
      (description "Capacitance:100nF Tolerance:±10% Tolerance:±10% Voltage Rating:25V Temperature Coefficient:X5R")
      (fields
        (field (name "Manufacturer Part") "CL05A104KA5NNNC")
        (field (name "Manufacturer") "SAMSUNG(三星)")
      )
      (libsource (lib "easyedapro") (part "CL05A104KA5NNNC"))
    )
    (comp (ref "C45")
      (value "2.2nF")
      (footprint "easyedapro:C0402")
      (fields
        (field (name "Manufacturer Part") "CC0402KRX7R8BB222")
        (field (name "Manufacturer") "YAGEO(国巨)")
      )
      (libsource (lib "easyedapro") (part "CC0402KRX7R8BB222"))
    )
    (comp (ref "C46")
      (value "10uF")
      (footprint "easyedapro:C0603")
      (description "Capacitance:10uF Tolerance:±10% Tolerance:±10% Voltage Rating:10V Temperature Coefficient:X5R")
      (fields
        (field (name "Manufacturer Part") "CL10A106KP8NNNC")
        (field (name "Manufacturer") "SAMSUNG(三星)")
      )
      (libsource (lib "easyedapro") (part "CL10A106KP8NNNC"))
    )
    (comp (ref "C47")
      (value "100nF")
      (footprint "easyedapro:C0402")
      (description "Capacitance:100nF Tolerance:±10% Tolerance:±10% Voltage Rating:16V Temperature Coefficient:X7R")
      (fields
        (field (name "Manufacturer Part") "CL05B104KO5NNNC")
        (field (name "Manufacturer") "SAMSUNG(三星)")
      )
      (libsource (lib "easyedapro") (part "CL05B104KO5NNNC"))
    )
    (comp (ref "C48")
      (value "2.2nF")
      (footprint "easyedapro:C0402")
      (description "Capacitance:2.2nF Tolerance:±10% Tolerance:±10% Voltage Rating:50V Temperature Coefficient:X7R")
      (fields (field (name "Manufacturer Part") "0402B222K500NT") (field (name "Manufacturer") "FH(风华)"))
      (libsource (lib "easyedapro") (part "0402B222K500NT"))
    )
    (comp (ref "C49")
      (value "100nF")
      (footprint "easyedapro:C0402")
      (description "Capacitance:100nF Tolerance:±10% Tolerance:±10% Voltage Rating:16V Temperature Coefficient:X7R")
      (fields
        (field (name "Manufacturer Part") "CL05B104KO5NNNC")
        (field (name "Manufacturer") "SAMSUNG(三星)")
      )
      (libsource (lib "easyedapro") (part "CL05B104KO5NNNC"))
    )
    (comp (ref "C50")
      (value "100nF")
      (footprint "easyedapro:C0402")
      (description "Capacitance:100nF Tolerance:±10% Tolerance:±10% Voltage Rating:16V Temperature Coefficient:X7R")
      (fields
        (field (name "Manufacturer Part") "CL05B104KO5NNNC")
        (field (name "Manufacturer") "SAMSUNG(三星)")
      )
      (libsource (lib "easyedapro") (part "CL05B104KO5NNNC"))
    )
    (comp (ref "C51")
      (value "2.2nF")
      (footprint "easyedapro:C0402")
      (description "Capacitance:2.2nF Tolerance:±10% Tolerance:±10% Voltage Rating:50V Temperature Coefficient:X7R")
      (fields (field (name "Manufacturer Part") "0402B222K500NT") (field (name "Manufacturer") "FH(风华)"))
      (libsource (lib "easyedapro") (part "0402B222K500NT"))
    )
    (comp (ref "C53")
      (value "100nF")
      (footprint "easyedapro:C0402")
      (description "Capacitance:100nF Tolerance:±10% Tolerance:±10% Voltage Rating:16V Temperature Coefficient:X7R")
      (fields
        (field (name "Manufacturer Part") "CL05B104KO5NNNC")
        (field (name "Manufacturer") "SAMSUNG(三星)")
      )
      (libsource (lib "easyedapro") (part "CL05B104KO5NNNC"))
    )
    (comp (ref "C54")
      (value "2.2nF")
      (footprint "easyedapro:C0402")
      (description "Capacitance:2.2nF Tolerance:±10% Tolerance:±10% Voltage Rating:50V Temperature Coefficient:X7R")
      (fields (field (name "Manufacturer Part") "0402B222K500NT") (field (name "Manufacturer") "FH(风华)"))
      (libsource (lib "easyedapro") (part "0402B222K500NT"))
    )
    (comp (ref "C55")
      (value "100nF")
      (footprint "easyedapro:C0402")
      (description "Capacitance:100nF Tolerance:±10% Tolerance:±10% Voltage Rating:16V Temperature Coefficient:X7R")
      (fields
        (field (name "Manufacturer Part") "CL05B104KO5NNNC")
        (field (name "Manufacturer") "SAMSUNG(三星)")
      )
      (libsource (lib "easyedapro") (part "CL05B104KO5NNNC"))
    )
    (comp (ref "C56")
      (value "100nF")
      (footprint "easyedapro:C0402")
      (description "Capacitance:100nF Tolerance:±10% Tolerance:±10% Voltage Rating:16V Temperature Coefficient:X7R")
      (fields
        (field (name "Manufacturer Part") "CL05B104KO5NNNC")
        (field (name "Manufacturer") "SAMSUNG(三星)")
      )
      (libsource (lib "easyedapro") (part "CL05B104KO5NNNC"))
    )
    (comp (ref "C57")
      (value "2.2nF")
      (footprint "easyedapro:C0402")
      (description "Capacitance:2.2nF Tolerance:±10% Tolerance:±10% Voltage Rating:50V Temperature Coefficient:X7R")
      (fields (field (name "Manufacturer Part") "0402B222K500NT") (field (name "Manufacturer") "FH(风华)"))
      (libsource (lib "easyedapro") (part "0402B222K500NT"))
    )
    (comp (ref "C58")
      (value "100nF")
      (footprint "easyedapro:C0402")
      (description "Capacitance:100nF Tolerance:±10% Tolerance:±10% Voltage Rating:16V Temperature Coefficient:X7R")
      (fields
        (field (name "Manufacturer Part") "CL05B104KO5NNNC")
        (field (name "Manufacturer") "SAMSUNG(三星)")
      )
      (libsource (lib "easyedapro") (part "CL05B104KO5NNNC"))
    )
    (comp (ref "CN3")
      (value "S2B-PH-SM4-TB(LF)(SN)")
      (footprint "easyedapro:CONN-SMD_P2.00_S2B-PH-SM4-TB-LF-SN")
      (fields (field (name "Manufacturer") "JST"))
      (libsource (lib "easyedapro") (part "S2B-PH-SM4-TB(LF)(SN)"))
    )
    (comp (ref "CN4")
      (value "S2B-PH-SM4-TB(LF)(SN)")
      (footprint "easyedapro:CONN-SMD_P2.00_S2B-PH-SM4-TB-LF-SN")
      (fields (field (name "Manufacturer") "JST"))
      (libsource (lib "easyedapro") (part "S2B-PH-SM4-TB(LF)(SN)"))
    )
    (comp (ref "CN5")
      (value "S2B-PH-SM4-TB(LF)(SN)")
      (footprint "easyedapro:CONN-SMD_P2.00_S2B-PH-SM4-TB-LF-SN")
      (fields (field (name "Manufacturer") "JST"))
      (libsource (lib "easyedapro") (part "S2B-PH-SM4-TB(LF)(SN)"))
    )
    (comp (ref "CN6")
      (value "S2B-PH-SM4-TB(LF)(SN)")
      (footprint "easyedapro:CONN-SMD_P2.00_S2B-PH-SM4-TB-LF-SN")
      (fields (field (name "Manufacturer") "JST"))
      (libsource (lib "easyedapro") (part "S2B-PH-SM4-TB(LF)(SN)"))
    )
    (comp (ref "Q5")
      (value "AO3400")
      (footprint "easyedapro:SOT-23-3_L2.9-W1.3-P1.90-LS2.4-BR")
      (description "Number:1 N-channel Drain to Source Voltage:30V Current - Continuous Drain(Id):5.8A")
      (fields (field (name "Manufacturer") "FOSAN(富捷/富信)"))
      (libsource (lib "easyedapro") (part "AO3400_C20628874"))
    )
    (comp (ref "Q6")
      (value "AO3400")
      (footprint "easyedapro:SOT-23-3_L2.9-W1.3-P1.90-LS2.4-BR")
      (description "Number:1 N-channel Drain to Source Voltage:30V Current - Continuous Drain(Id):5.8A")
      (fields (field (name "Manufacturer") "FOSAN(富捷/富信)"))
      (libsource (lib "easyedapro") (part "AO3400_C20628874"))
    )
    (comp (ref "Q7")
      (value "AO3400")
      (footprint "easyedapro:SOT-23-3_L2.9-W1.3-P1.90-LS2.4-BR")
      (description "Number:1 N-channel Drain to Source Voltage:30V Current - Continuous Drain(Id):5.8A")
      (fields (field (name "Manufacturer") "FOSAN(富捷/富信)"))
      (libsource (lib "easyedapro") (part "AO3400_C20628874"))
    )
    (comp (ref "Q8")
      (value "AO3400")
      (footprint "easyedapro:SOT-23-3_L2.9-W1.3-P1.90-LS2.4-BR")
      (description "Number:1 N-channel Drain to Source Voltage:30V Current - Continuous Drain(Id):5.8A")
      (fields (field (name "Manufacturer") "FOSAN(富捷/富信)"))
      (libsource (lib "easyedapro") (part "AO3400_C20628874"))
    )
    (comp (ref "R17")
      (value "22Ω")
      (footprint "easyedapro:R0402")
      (fields (field (name "Manufacturer Part") "RC0402FR-0722RL") (field (name "Manufacturer") "YAGEO(国巨)"))
      (libsource (lib "easyedapro") (part "RC0402FR-0722RL"))
    )
    (comp (ref "R18")
      (value "100kΩ")
      (footprint "easyedapro:R0402")
      (fields
        (field (name "Manufacturer Part") "0402WGF1003TCE")
        (field (name "Manufacturer") "UNI-ROYAL(厚声)")
      )
      (libsource (lib "easyedapro") (part "0402WGF1003TCE"))
    )
    (comp (ref "R19")
      (value "10Ω")
      (footprint "easyedapro:R0402")
      (fields
        (field (name "Manufacturer Part") "0402WGF100JTCE")
        (field (name "Manufacturer") "UNI-ROYAL(厚声)")
      )
      (libsource (lib "easyedapro") (part "0402WGF100JTCE"))
    )
    (comp (ref "R20")
      (value "22Ω")
      (footprint "easyedapro:R0402")
      (fields (field (name "Manufacturer Part") "RC0402FR-0722RL") (field (name "Manufacturer") "YAGEO(国巨)"))
      (libsource (lib "easyedapro") (part "RC0402FR-0722RL"))
    )
    (comp (ref "R21")
      (value "22Ω")
      (footprint "easyedapro:R0402")
      (fields (field (name "Manufacturer Part") "RC0402FR-0722RL") (field (name "Manufacturer") "YAGEO(国巨)"))
      (libsource (lib "easyedapro") (part "RC0402FR-0722RL"))
    )
    (comp (ref "R22")
      (value "100kΩ")
      (footprint "easyedapro:R0402")
      (fields
        (field (name "Manufacturer Part") "0402WGF1003TCE")
        (field (name "Manufacturer") "UNI-ROYAL(厚声)")
      )
      (libsource (lib "easyedapro") (part "0402WGF1003TCE"))
    )
    (comp (ref "R23")
      (value "10Ω")
      (footprint "easyedapro:R0402")
      (fields
        (field (name "Manufacturer Part") "0402WGF100JTCE")
        (field (name "Manufacturer") "UNI-ROYAL(厚声)")
      )
      (libsource (lib "easyedapro") (part "0402WGF100JTCE"))
    )
    (comp (ref "R24")
      (value "22Ω")
      (footprint "easyedapro:R0402")
      (fields (field (name "Manufacturer Part") "RC0402FR-0722RL") (field (name "Manufacturer") "YAGEO(国巨)"))
      (libsource (lib "easyedapro") (part "RC0402FR-0722RL"))
    )
    (comp (ref "R25")
      (value "22Ω")
      (footprint "easyedapro:R0402")
      (fields (field (name "Manufacturer Part") "RC0402FR-0722RL") (field (name "Manufacturer") "YAGEO(国巨)"))
      (libsource (lib "easyedapro") (part "RC0402FR-0722RL"))
    )
    (comp (ref "R26")
      (value "100kΩ")
      (footprint "easyedapro:R0402")
      (fields
        (field (name "Manufacturer Part") "0402WGF1003TCE")
        (field (name "Manufacturer") "UNI-ROYAL(厚声)")
      )
      (libsource (lib "easyedapro") (part "0402WGF1003TCE"))
    )
    (comp (ref "R27")
      (value "10Ω")
      (footprint "easyedapro:R0402")
      (fields
        (field (name "Manufacturer Part") "0402WGF100JTCE")
        (field (name "Manufacturer") "UNI-ROYAL(厚声)")
      )
      (libsource (lib "easyedapro") (part "0402WGF100JTCE"))
    )
    (comp (ref "R28")
      (value "22Ω")
      (footprint "easyedapro:R0402")
      (fields (field (name "Manufacturer Part") "RC0402FR-0722RL") (field (name "Manufacturer") "YAGEO(国巨)"))
      (libsource (lib "easyedapro") (part "RC0402FR-0722RL"))
    )
    (comp (ref "R29")
      (value "22Ω")
      (footprint "easyedapro:R0402")
      (fields (field (name "Manufacturer Part") "RC0402FR-0722RL") (field (name "Manufacturer") "YAGEO(国巨)"))
      (libsource (lib "easyedapro") (part "RC0402FR-0722RL"))
    )
    (comp (ref "R30")
      (value "100kΩ")
      (footprint "easyedapro:R0402")
      (fields
        (field (name "Manufacturer Part") "0402WGF1003TCE")
        (field (name "Manufacturer") "UNI-ROYAL(厚声)")
      )
      (libsource (lib "easyedapro") (part "0402WGF1003TCE"))
    )
    (comp (ref "R31")
      (value "10Ω")
      (footprint "easyedapro:R0402")
      (fields
        (field (name "Manufacturer Part") "0402WGF100JTCE")
        (field (name "Manufacturer") "UNI-ROYAL(厚声)")
      )
      (libsource (lib "easyedapro") (part "0402WGF100JTCE"))
    )
    (comp (ref "R32")
      (value "22Ω")
      (footprint "easyedapro:R0402")
      (fields (field (name "Manufacturer Part") "RC0402FR-0722RL") (field (name "Manufacturer") "YAGEO(国巨)"))
      (libsource (lib "easyedapro") (part "RC0402FR-0722RL"))
    )
    (comp (ref "R33")
      (value "100kΩ")
      (footprint "easyedapro:R0402")
      (fields
        (field (name "Manufacturer Part") "0402WGF1003TCE")
        (field (name "Manufacturer") "UNI-ROYAL(厚声)")
      )
      (libsource (lib "easyedapro") (part "0402WGF1003TCE"))
    )
    (comp (ref "R34")
      (value "100kΩ")
      (footprint "easyedapro:R0402")
      (fields
        (field (name "Manufacturer Part") "0402WGF1003TCE")
        (field (name "Manufacturer") "UNI-ROYAL(厚声)")
      )
      (libsource (lib "easyedapro") (part "0402WGF1003TCE"))
    )
    (comp (ref "R35")
      (value "100kΩ")
      (footprint "easyedapro:R0402")
      (fields
        (field (name "Manufacturer Part") "0402WGF1003TCE")
        (field (name "Manufacturer") "UNI-ROYAL(厚声)")
      )
      (libsource (lib "easyedapro") (part "0402WGF1003TCE"))
    )
    (comp (ref "R36")
      (value "100kΩ")
      (footprint "easyedapro:R0402")
      (fields
        (field (name "Manufacturer Part") "0402WGF1003TCE")
        (field (name "Manufacturer") "UNI-ROYAL(厚声)")
      )
      (libsource (lib "easyedapro") (part "0402WGF1003TCE"))
    )
    (comp (ref "R37")
      (value "10kΩ")
      (footprint "easyedapro:R0402")
      (fields
        (field (name "Manufacturer Part") "0402WGF1002TCE")
        (field (name "Manufacturer") "UNI-ROYAL(厚声)")
      )
      (libsource (lib "easyedapro") (part "0402WGF1002TCE"))
    )
    (comp (ref "R38")
      (value "4.7kΩ")
      (footprint "easyedapro:R0402")
      (fields
        (field (name "Manufacturer Part") "0402WGF4701TCE")
        (field (name "Manufacturer") "UNI-ROYAL(厚声)")
      )
      (libsource (lib "easyedapro") (part "0402WGF4701TCE"))
    )
    (comp (ref "R39")
      (value "470kΩ")
      (footprint "easyedapro:R0603")
      (fields
        (field (name "Manufacturer Part") "0603WAF4703T5E")
        (field (name "Manufacturer") "UNI-ROYAL(厚声)")
      )
      (libsource (lib "easyedapro") (part "0603WAF4703T5E"))
    )
    (comp (ref "R40")
      (value "100kΩ")
      (footprint "easyedapro:R0402")
      (fields
        (field (name "Manufacturer Part") "0402WGF1003TCE")
        (field (name "Manufacturer") "UNI-ROYAL(厚声)")
      )
      (libsource (lib "easyedapro") (part "0402WGF1003TCE"))
    )
    (comp (ref "R41")
      (value "100kΩ")
      (footprint "easyedapro:R0402")
      (fields
        (field (name "Manufacturer Part") "0402WGF1003TCE")
        (field (name "Manufacturer") "UNI-ROYAL(厚声)")
      )
      (libsource (lib "easyedapro") (part "0402WGF1003TCE"))
    )
    (comp (ref "R42")
      (value "10kΩ")
      (footprint "easyedapro:R0402")
      (fields
        (field (name "Manufacturer Part") "0402WGF1002TCE")
        (field (name "Manufacturer") "UNI-ROYAL(厚声)")
      )
      (libsource (lib "easyedapro") (part "0402WGF1002TCE"))
    )
    (comp (ref "R43")
      (value "4.7kΩ")
      (footprint "easyedapro:R0402")
      (fields
        (field (name "Manufacturer Part") "0402WGF4701TCE")
        (field (name "Manufacturer") "UNI-ROYAL(厚声)")
      )
      (libsource (lib "easyedapro") (part "0402WGF4701TCE"))
    )
    (comp (ref "R44")
      (value "470kΩ")
      (footprint "easyedapro:R0603")
      (fields
        (field (name "Manufacturer Part") "0603WAF4703T5E")
        (field (name "Manufacturer") "UNI-ROYAL(厚声)")
      )
      (libsource (lib "easyedapro") (part "0603WAF4703T5E"))
    )
    (comp (ref "R45")
      (value "100kΩ")
      (footprint "easyedapro:R0402")
      (fields
        (field (name "Manufacturer Part") "0402WGF1003TCE")
        (field (name "Manufacturer") "UNI-ROYAL(厚声)")
      )
      (libsource (lib "easyedapro") (part "0402WGF1003TCE"))
    )
    (comp (ref "R46")
      (value "100kΩ")
      (footprint "easyedapro:R0402")
      (fields
        (field (name "Manufacturer Part") "0402WGF1003TCE")
        (field (name "Manufacturer") "UNI-ROYAL(厚声)")
      )
      (libsource (lib "easyedapro") (part "0402WGF1003TCE"))
    )
    (comp (ref "R47")
      (value "10kΩ")
      (footprint "easyedapro:R0402")
      (fields
        (field (name "Manufacturer Part") "0402WGF1002TCE")
        (field (name "Manufacturer") "UNI-ROYAL(厚声)")
      )
      (libsource (lib "easyedapro") (part "0402WGF1002TCE"))
    )
    (comp (ref "R48")
      (value "4.7kΩ")
      (footprint "easyedapro:R0402")
      (fields
        (field (name "Manufacturer Part") "0402WGF4701TCE")
        (field (name "Manufacturer") "UNI-ROYAL(厚声)")
      )
      (libsource (lib "easyedapro") (part "0402WGF4701TCE"))
    )
    (comp (ref "R49")
      (value "470kΩ")
      (footprint "easyedapro:R0603")
      (fields
        (field (name "Manufacturer Part") "0603WAF4703T5E")
        (field (name "Manufacturer") "UNI-ROYAL(厚声)")
      )
      (libsource (lib "easyedapro") (part "0603WAF4703T5E"))
    )
    (comp (ref "R50")
      (value "100kΩ")
      (footprint "easyedapro:R0402")
      (fields
        (field (name "Manufacturer Part") "0402WGF1003TCE")
        (field (name "Manufacturer") "UNI-ROYAL(厚声)")
      )
      (libsource (lib "easyedapro") (part "0402WGF1003TCE"))
    )
    (comp (ref "R51")
      (value "100kΩ")
      (footprint "easyedapro:R0402")
      (fields
        (field (name "Manufacturer Part") "0402WGF1003TCE")
        (field (name "Manufacturer") "UNI-ROYAL(厚声)")
      )
      (libsource (lib "easyedapro") (part "0402WGF1003TCE"))
    )
    (comp (ref "R52")
      (value "10kΩ")
      (footprint "easyedapro:R0402")
      (fields
        (field (name "Manufacturer Part") "0402WGF1002TCE")
        (field (name "Manufacturer") "UNI-ROYAL(厚声)")
      )
      (libsource (lib "easyedapro") (part "0402WGF1002TCE"))
    )
    (comp (ref "R53")
      (value "4.7kΩ")
      (footprint "easyedapro:R0402")
      (fields
        (field (name "Manufacturer Part") "0402WGF4701TCE")
        (field (name "Manufacturer") "UNI-ROYAL(厚声)")
      )
      (libsource (lib "easyedapro") (part "0402WGF4701TCE"))
    )
    (comp (ref "R54")
      (value "470kΩ")
      (footprint "easyedapro:R0603")
      (fields
        (field (name "Manufacturer Part") "0603WAF4703T5E")
        (field (name "Manufacturer") "UNI-ROYAL(厚声)")
      )
      (libsource (lib "easyedapro") (part "0603WAF4703T5E"))
    )
    (comp (ref "U10")
      (value "TPMCP6022T-I/SN")
      (footprint "easyedapro:SOP-8_L4.9-W3.9-P1.27-LS6.0-BL")
      (fields (field (name "Manufacturer") "TECH PUBLIC(台舟)"))
      (libsource (lib "easyedapro") (part "TPMCP6022T-I/SN"))
    )
    (comp (ref "U11")
      (value "TPMCP6022T-I/SN")
      (footprint "easyedapro:SOP-8_L4.9-W3.9-P1.27-LS6.0-BL")
      (fields (field (name "Manufacturer") "TECH PUBLIC(台舟)"))
      (libsource (lib "easyedapro") (part "TPMCP6022T-I/SN"))
    )
    (comp (ref "U12")
      (value "LM311DR")
      (footprint "easyedapro:SOIC-8_L5.0-W4.0-P1.27-LS6.0-BL")
      (fields (field (name "Manufacturer") "TI(德州仪器)"))
      (libsource (lib "easyedapro") (part "LM311DR"))
    )
    (comp (ref "U13")
      (value "LM311DR")
      (footprint "easyedapro:SOIC-8_L5.0-W4.0-P1.27-LS6.0-BL")
      (fields (field (name "Manufacturer") "TI(德州仪器)"))
      (libsource (lib "easyedapro") (part "LM311DR"))
    )
    (comp (ref "U14")
      (value "LM311DR")
      (footprint "easyedapro:SOIC-8_L5.0-W4.0-P1.27-LS6.0-BL")
      (fields (field (name "Manufacturer") "TI(德州仪器)"))
      (libsource (lib "easyedapro") (part "LM311DR"))
    )
    (comp (ref "U15")
      (value "LM311DR")
      (footprint "easyedapro:SOIC-8_L5.0-W4.0-P1.27-LS6.0-BL")
      (fields (field (name "Manufacturer") "TI(德州仪器)"))
      (libsource (lib "easyedapro") (part "LM311DR"))
    )
    (comp (ref "C59")
      (value "10uF")
      (footprint "easyedapro:C0603")
      (description "Capacitance:10uF Tolerance:±10% Tolerance:±10% Voltage Rating:10V Temperature Coefficient:X5R")
      (fields
        (field (name "Manufacturer Part") "CL10A106KP8NNNC")
        (field (name "Manufacturer") "SAMSUNG(三星)")
      )
      (libsource (lib "easyedapro") (part "CL10A106KP8NNNC"))
    )
    (comp (ref "C60")
      (value "1uF")
      (footprint "easyedapro:C0603")
      (description "Capacitance:1uF Tolerance:±10% Tolerance:±10% Voltage Rating:50V Temperature Coefficient:X5R")
      (fields
        (field (name "Manufacturer Part") "CGA0603X5R105K500JT")
        (field (name "Manufacturer") "HRE(芯声)")
      )
      (libsource (lib "easyedapro") (part "CGA0603X5R105K500JT"))
    )
    (comp (ref "C61")
      (value "100nF")
      (footprint "easyedapro:C0402")
      (description "Capacitance:100nF Tolerance:±10% Tolerance:±10% Voltage Rating:16V Temperature Coefficient:X7R")
      (fields
        (field (name "Manufacturer Part") "CL05B104KO5NNNC")
        (field (name "Manufacturer") "SAMSUNG(三星)")
      )
      (libsource (lib "easyedapro") (part "CL05B104KO5NNNC"))
    )
    (comp (ref "C62")
      (value "1uF")
      (footprint "easyedapro:C0603")
      (description "Capacitance:1uF Tolerance:±10% Tolerance:±10% Voltage Rating:50V Temperature Coefficient:X5R")
      (fields
        (field (name "Manufacturer Part") "CGA0603X5R105K500JT")
        (field (name "Manufacturer") "HRE(芯声)")
      )
      (libsource (lib "easyedapro") (part "CGA0603X5R105K500JT"))
    )
    (comp (ref "F3")
      (value "4.7kΩ")
      (footprint "easyedapro:RES-ARRAY-SMD_0404-4P-L1.0-W1.0-BL")
      (fields (field (name "Manufacturer Part") "YC122-JR-074K7L") (field (name "Manufacturer") "YAGEO(国巨)"))
      (libsource (lib "easyedapro") (part "YC122-JR-074K7L"))
    )
    (comp (ref "R55")
      (value "10kΩ")
      (footprint "easyedapro:R0402")
      (fields
        (field (name "Manufacturer Part") "0402WGF1002TCE")
        (field (name "Manufacturer") "UNI-ROYAL(厚声)")
      )
      (libsource (lib "easyedapro") (part "0402WGF1002TCE"))
    )
    (comp (ref "R56")
      (value "10kΩ")
      (footprint "easyedapro:R0402")
      (fields
        (field (name "Manufacturer Part") "0402WGF1002TCE")
        (field (name "Manufacturer") "UNI-ROYAL(厚声)")
      )
      (libsource (lib "easyedapro") (part "0402WGF1002TCE"))
    )
    (comp (ref "R57")
      (value "10kΩ")
      (footprint "easyedapro:R0402")
      (fields
        (field (name "Manufacturer Part") "0402WGF1002TCE")
        (field (name "Manufacturer") "UNI-ROYAL(厚声)")
      )
      (libsource (lib "easyedapro") (part "0402WGF1002TCE"))
    )
    (comp (ref "R60")
      (value "10kΩ")
      (footprint "easyedapro:R0402")
      (fields
        (field (name "Manufacturer Part") "0402WGF1002TCE")
        (field (name "Manufacturer") "UNI-ROYAL(厚声)")
      )
      (libsource (lib "easyedapro") (part "0402WGF1002TCE"))
    )
    (comp (ref "RN1")
      (value "100Ω")
      (footprint "easyedapro:RES-ARRAY-SMD_0804-8P-L2.0-W1.0-BL")
      (fields (field (name "Manufacturer Part") "YC124-JR-07100RL") (field (name "Manufacturer") "YAGEO(国巨)"))
      (libsource (lib "easyedapro") (part "YC124-JR-07100RL"))
    )
    (comp (ref "RN2")
      (value "100Ω")
      (footprint "easyedapro:RES-ARRAY-SMD_0804-8P-L2.0-W1.0-BL")
      (fields (field (name "Manufacturer Part") "YC124-JR-07100RL") (field (name "Manufacturer") "YAGEO(国巨)"))
      (libsource (lib "easyedapro") (part "YC124-JR-07100RL"))
    )
    (comp (ref "SW2")
      (value "HX-3x6x2.5-X SMD tact Switch")
      (footprint "easyedapro:SW-SMD_HX-3X6X2.5-X")
      (fields (field (name "Manufacturer") "hanxia(韩下)"))
      (libsource (lib "easyedapro") (part "HX-3X6X2.5-X SMD TACT SWITCH"))
    )
    (comp (ref "SW3")
      (value "HX-3x6x2.5-X SMD tact Switch")
      (footprint "easyedapro:SW-SMD_HX-3X6X2.5-X")
      (fields (field (name "Manufacturer") "hanxia(韩下)"))
      (libsource (lib "easyedapro") (part "HX-3X6X2.5-X SMD TACT SWITCH"))
    )
    (comp (ref "U16")
      (value "2.4GHz")
      (footprint "easyedapro:WIFIM-SMD_ESP32-C3-MINI-1")
      (fields
        (field (name "Manufacturer Part") "ESP32-C3-MINI-1-H4")
        (field (name "Manufacturer") "ESPRESSIF(乐鑫)")
      )
      (libsource (lib "easyedapro") (part "ESP32-C3-MINI-1-H4(4MB)"))
    )
    (comp (ref "U17")
      (value "SM06B-SRSS-TB(LF)(SN)")
      (footprint "easyedapro:CONN-SMD_SM06B-SRSS-TB-LF-SN")
      (fields (field (name "Manufacturer") "JST"))
      (libsource (lib "easyedapro") (part "SM06B-SRSS-TB(LF)(SN)"))
    )
  )
  (nets
    (net (code "1") (name "2V5_REF") (class "Default")
      (node (ref "C46") (pin "2") (pinfunction "2_2") (pintype "unspecified"))
      (node (ref "C47") (pin "2") (pinfunction "2_2") (pintype "unspecified"))
      (node (ref "R33") (pin "1") (pinfunction "1_1") (pintype "input"))
      (node (ref "R34") (pin "2") (pinfunction "2_2") (pintype "input"))
      (node (ref "R35") (pin "1") (pinfunction "1_1") (pintype "input"))
      (node (ref "R37") (pin "1") (pinfunction "1_1") (pintype "input"))
      (node (ref "R40") (pin "1") (pinfunction "1_1") (pintype "input"))
      (node (ref "R42") (pin "1") (pinfunction "1_1") (pintype "input"))
      (node (ref "R45") (pin "1") (pinfunction "1_1") (pintype "input"))
      (node (ref "R47") (pin "1") (pinfunction "1_1") (pintype "input"))
      (node (ref "R50") (pin "1") (pinfunction "1_1") (pintype "input"))
      (node (ref "R52") (pin "1") (pinfunction "1_1") (pintype "input"))
      (node (ref "U12") (pin "3") (pinfunction "IN-_3") (pintype "unspecified"))
      (node (ref "U13") (pin "3") (pinfunction "IN-_3") (pintype "unspecified"))
      (node (ref "U14") (pin "3") (pinfunction "IN-_3") (pintype "unspecified"))
      (node (ref "U15") (pin "3") (pinfunction "IN-_3") (pintype "unspecified"))
    )
    (net (code "2") (name "3V3_SYS") (class "Default")
      (node (ref "C17") (pin "2") (pinfunction "2_2") (pintype "unspecified"))
      (node (ref "C18") (pin "2") (pinfunction "2_2") (pintype "unspecified"))
      (node (ref "C59") (pin "2") (pinfunction "2_2") (pintype "unspecified"))
      (node (ref "C60") (pin "2") (pinfunction "2_2") (pintype "unspecified"))
      (node (ref "C61") (pin "2") (pinfunction "2_2") (pintype "unspecified"))
      (node (ref "F3") (pin "3") (pinfunction "3_3") (pintype "input"))
      (node (ref "F3") (pin "4") (pinfunction "4_4") (pintype "input"))
      (node (ref "R38") (pin "2") (pinfunction "2_2") (pintype "input"))
      (node (ref "R43") (pin "2") (pinfunction "2_2") (pintype "input"))
      (node (ref "R48") (pin "2") (pinfunction "2_2") (pintype "input"))
      (node (ref "R53") (pin "2") (pinfunction "2_2") (pintype "input"))
      (node (ref "R55") (pin "1") (pinfunction "1_1") (pintype "input"))
      (node (ref "R56") (pin "1") (pinfunction "1_1") (pintype "input"))
      (node (ref "R57") (pin "1") (pinfunction "1_1") (pintype "input"))
      (node (ref "R60") (pin "1") (pinfunction "1_1") (pintype "input"))
      (node (ref "U1") (pin "5") (pinfunction "VOUT_5") (pintype "unspecified"))
      (node (ref "U16") (pin "3") (pinfunction "3V3_3") (pintype "unspecified"))
      (node (ref "U17") (pin "2") (pinfunction "2_2") (pintype "unspecified"))
    )
    (net (code "3") (name "5V_SYS") (class "Default")
      (node (ref "C23") (pin "2") (pinfunction "2_2") (pintype "unspecified"))
      (node (ref "C25") (pin "2") (pinfunction "2_2") (pintype "unspecified"))
      (node (ref "C49") (pin "2") (pinfunction "2_2") (pintype "unspecified"))
      (node (ref "C50") (pin "2") (pinfunction "2_2") (pintype "unspecified"))
      (node (ref "C53") (pin "2") (pinfunction "2_2") (pintype "unspecified"))
      (node (ref "C55") (pin "2") (pinfunction "2_2") (pintype "unspecified"))
      (node (ref "C56") (pin "2") (pinfunction "2_2") (pintype "unspecified"))
      (node (ref "C58") (pin "2") (pinfunction "2_2") (pintype "unspecified"))
      (node (ref "D3") (pin "1") (pinfunction "C_1") (pintype "unspecified"))
      (node (ref "R14") (pin "2") (pinfunction "2_2") (pintype "unspecified"))
      (node (ref "R33") (pin "2") (pinfunction "2_2") (pintype "input"))
      (node (ref "U10") (pin "8") (pinfunction "+VS_8") (pintype "unspecified"))
      (node (ref "U11") (pin "8") (pinfunction "+VS_8") (pintype "unspecified"))
      (node (ref "U12") (pin "6") (pinfunction "BALSTRB_6") (pintype "unspecified"))
      (node (ref "U12") (pin "8") (pinfunction "VCC+_8") (pintype "unspecified"))
      (node (ref "U13") (pin "6") (pinfunction "BALSTRB_6") (pintype "unspecified"))
      (node (ref "U13") (pin "8") (pinfunction "VCC+_8") (pintype "unspecified"))
      (node (ref "U14") (pin "6") (pinfunction "BALSTRB_6") (pintype "unspecified"))
      (node (ref "U14") (pin "8") (pinfunction "VCC+_8") (pintype "unspecified"))
      (node (ref "U15") (pin "6") (pinfunction "BALSTRB_6") (pintype "unspecified"))
      (node (ref "U15") (pin "8") (pinfunction "VCC+_8") (pintype "unspecified"))
    )
    (net (code "4") (name "22V_SYS") (class "Default")
      (node (ref "C31") (pin "2") (pinfunction "2_2") (pintype "unspecified"))
      (node (ref "C33") (pin "2") (pinfunction "2_2") (pintype "unspecified"))
      (node (ref "C34") (pin "2") (pinfunction "2_2") (pintype "unspecified"))
      (node (ref "C35") (pin "2") (pinfunction "2_2") (pintype "input"))
      (node (ref "C37") (pin "2") (pinfunction "2_2") (pintype "unspecified"))
      (node (ref "C38") (pin "2") (pinfunction "2_2") (pintype "input"))
      (node (ref "C40") (pin "2") (pinfunction "2_2") (pintype "unspecified"))
      (node (ref "C41") (pin "2") (pinfunction "2_2") (pintype "input"))
      (node (ref "C43") (pin "2") (pinfunction "2_2") (pintype "unspecified"))
      (node (ref "C44") (pin "2") (pinfunction "2_2") (pintype "input"))
      (node (ref "D4") (pin "1") (pinfunction "C_1") (pintype "unspecified"))
      (node (ref "R15") (pin "2") (pinfunction "2_2") (pintype "input"))
      (node (ref "R19") (pin "1") (pinfunction "1_1") (pintype "input"))
      (node (ref "R23") (pin "1") (pinfunction "1_1") (pintype "input"))
      (node (ref "R27") (pin "1") (pinfunction "1_1") (pintype "input"))
      (node (ref "R31") (pin "1") (pinfunction "1_1") (pintype "input"))
    )
    (net (code "5") (name "CRG") (class "Default")
      (node (ref "R5") (pin "1") (pinfunction "1_1") (pintype "input"))
      (node (ref "U4") (pin "7") (pinfunction "CHRG#_7") (pintype "unspecified"))
    )
    (net (code "6") (name "DNE") (class "Default")
      (node (ref "R4") (pin "1") (pinfunction "1_1") (pintype "input"))
      (node (ref "U4") (pin "6") (pinfunction "DONE#_6") (pintype "unspecified"))
    )
    (net (code "7") (name "GND") (class "Default")
      (node (ref "B1") (pin "2") (pinfunction "2_2") (pintype "input"))
      (node (ref "C10") (pin "1") (pinfunction "1_1") (pintype "unspecified"))
      (node (ref "C11") (pin "1") (pinfunction "1_1") (pintype "unspecified"))
      (node (ref "C12") (pin "1") (pinfunction "1_1") (pintype "unspecified"))
      (node (ref "C13") (pin "1") (pinfunction "1_1") (pintype "unspecified"))
      (node (ref "C15") (pin "1") (pinfunction "1_1") (pintype "unspecified"))
      (node (ref "C16") (pin "1") (pinfunction "1_1") (pintype "unspecified"))
      (node (ref "C17") (pin "1") (pinfunction "1_1") (pintype "unspecified"))
      (node (ref "C18") (pin "1") (pinfunction "1_1") (pintype "unspecified"))
      (node (ref "C21") (pin "1") (pinfunction "1_1") (pintype "unspecified"))
      (node (ref "C23") (pin "1") (pinfunction "1_1") (pintype "unspecified"))
      (node (ref "C24") (pin "1") (pinfunction "1_1") (pintype "unspecified"))
      (node (ref "C25") (pin "1") (pinfunction "1_1") (pintype "unspecified"))
      (node (ref "C3") (pin "1") (pinfunction "1_1") (pintype "unspecified"))
      (node (ref "C30") (pin "1") (pinfunction "1_1") (pintype "unspecified"))
      (node (ref "C31") (pin "1") (pinfunction "1_1") (pintype "unspecified"))
      (node (ref "C32") (pin "1") (pinfunction "1_1") (pintype "unspecified"))
      (node (ref "C33") (pin "1") (pinfunction "1_1") (pintype "unspecified"))
      (node (ref "C34") (pin "1") (pinfunction "1_1") (pintype "unspecified"))
      (node (ref "C35") (pin "1") (pinfunction "1_1") (pintype "input"))
      (node (ref "C36") (pin "1") (pinfunction "1_1") (pintype "input"))
      (node (ref "C37") (pin "1") (pinfunction "1_1") (pintype "unspecified"))
      (node (ref "C38") (pin "1") (pinfunction "1_1") (pintype "input"))
      (node (ref "C39") (pin "1") (pinfunction "1_1") (pintype "input"))
      (node (ref "C4") (pin "1") (pinfunction "1_1") (pintype "unspecified"))
      (node (ref "C40") (pin "1") (pinfunction "1_1") (pintype "unspecified"))
      (node (ref "C41") (pin "1") (pinfunction "1_1") (pintype "input"))
      (node (ref "C42") (pin "1") (pinfunction "1_1") (pintype "input"))
      (node (ref "C43") (pin "1") (pinfunction "1_1") (pintype "unspecified"))
      (node (ref "C44") (pin "1") (pinfunction "1_1") (pintype "input"))
      (node (ref "C45") (pin "1") (pinfunction "1_1") (pintype "input"))
      (node (ref "C46") (pin "1") (pinfunction "1_1") (pintype "unspecified"))
      (node (ref "C47") (pin "1") (pinfunction "1_1") (pintype "unspecified"))
      (node (ref "C49") (pin "1") (pinfunction "1_1") (pintype "unspecified"))
      (node (ref "C5") (pin "1") (pinfunction "1_1") (pintype "unspecified"))
      (node (ref "C50") (pin "1") (pinfunction "1_1") (pintype "unspecified"))
      (node (ref "C53") (pin "1") (pinfunction "1_1") (pintype "unspecified"))
      (node (ref "C55") (pin "1") (pinfunction "1_1") (pintype "unspecified"))
      (node (ref "C56") (pin "1") (pinfunction "1_1") (pintype "unspecified"))
      (node (ref "C58") (pin "1") (pinfunction "1_1") (pintype "unspecified"))
      (node (ref "C59") (pin "1") (pinfunction "1_1") (pintype "unspecified"))
      (node (ref "C6") (pin "1") (pinfunction "1_1") (pintype "unspecified"))
      (node (ref "C60") (pin "1") (pinfunction "1_1") (pintype "unspecified"))
      (node (ref "C61") (pin "1") (pinfunction "1_1") (pintype "unspecified"))
      (node (ref "C62") (pin "1") (pinfunction "1_1") (pintype "unspecified"))
      (node (ref "C7") (pin "1") (pinfunction "1_1") (pintype "unspecified"))
      (node (ref "C8") (pin "1") (pinfunction "1_1") (pintype "unspecified"))
      (node (ref "C9") (pin "1") (pinfunction "1_1") (pintype "unspecified"))
      (node (ref "CN1") (pin "2") (pinfunction "2_2") (pintype "unspecified"))
      (node (ref "CN2") (pin "2") (pinfunction "2_2") (pintype "unspecified"))
      (node (ref "D1") (pin "1") (pinfunction "A_1") (pintype "input"))
      (node (ref "Q1") (pin "1") (pinfunction "G_1") (pintype "unspecified"))
      (node (ref "Q3") (pin "2") (pinfunction "S_2") (pintype "unspecified"))
      (node (ref "Q4") (pin "2") (pinfunction "S_2") (pintype "unspecified"))
      (node (ref "Q5") (pin "2") (pinfunction "S_2") (pintype "unspecified"))
      (node (ref "Q6") (pin "2") (pinfunction "S_2") (pintype "unspecified"))
      (node (ref "Q7") (pin "2") (pinfunction "S_2") (pintype "unspecified"))
      (node (ref "Q8") (pin "2") (pinfunction "S_2") (pintype "unspecified"))
      (node (ref "R13") (pin "1") (pinfunction "1_1") (pintype "input"))
      (node (ref "R16") (pin "1") (pinfunction "1_1") (pintype "input"))
      (node (ref "R18") (pin "2") (pinfunction "2_2") (pintype "input"))
      (node (ref "R2") (pin "1") (pinfunction "1_1") (pintype "input"))
      (node (ref "R22") (pin "2") (pinfunction "2_2") (pintype "input"))
      (node (ref "R26") (pin "2") (pinfunction "2_2") (pintype "input"))
      (node (ref "R3") (pin "1") (pinfunction "1_1") (pintype "input"))
      (node (ref "R30") (pin "2") (pinfunction "2_2") (pintype "input"))
      (node (ref "R34") (pin "1") (pinfunction "1_1") (pintype "input"))
      (node (ref "R59") (pin "1") (pinfunction "1_1") (pintype "input"))
      (node (ref "R6") (pin "2") (pinfunction "2_2") (pintype "input"))
      (node (ref "SW1") (pin "2") (pinfunction "2_2") (pintype "unspecified"))
      (node (ref "SW2") (pin "1") (pinfunction "1_1") (pintype "unspecified"))
      (node (ref "SW3") (pin "1") (pinfunction "1_1") (pintype "unspecified"))
      (node (ref "U1") (pin "2") (pinfunction "GND_2") (pintype "unspecified"))
      (node (ref "U10") (pin "4") (pinfunction "-VS_4") (pintype "unspecified"))
      (node (ref "U11") (pin "4") (pinfunction "-VS_4") (pintype "unspecified"))
      (node (ref "U12") (pin "1") (pinfunction "EMIT/OUT_1") (pintype "unspecified"))
      (node (ref "U12") (pin "4") (pinfunction "VCC-_4") (pintype "unspecified"))
      (node (ref "U13") (pin "1") (pinfunction "EMIT/OUT_1") (pintype "unspecified"))
      (node (ref "U13") (pin "4") (pinfunction "VCC-_4") (pintype "unspecified"))
      (node (ref "U14") (pin "1") (pinfunction "EMIT/OUT_1") (pintype "unspecified"))
      (node (ref "U14") (pin "4") (pinfunction "VCC-_4") (pintype "unspecified"))
      (node (ref "U15") (pin "1") (pinfunction "EMIT/OUT_1") (pintype "unspecified"))
      (node (ref "U15") (pin "4") (pinfunction "VCC-_4") (pintype "unspecified"))
      (node (ref "U17") (pin "1") (pinfunction "1_1") (pintype "unspecified"))
      (node (ref "U2") (pin "2") (pinfunction "GND_2") (pintype "unspecified"))
      (node (ref "U4") (pin "3") (pinfunction "GND_3") (pintype "unspecified"))
      (node (ref "U5") (pin "5") (pinfunction "VSS_5") (pintype "unspecified"))
      (node (ref "U8") (pin "1") (pinfunction "GND_1") (pintype "unspecified"))
      (node (ref "U9") (pin "2") (pinfunction "GND_2") (pintype "unspecified"))
    )
    (net (code "8") (name "I2C_SCL") (class "Default")
      (node (ref "F3") (pin "1") (pinfunction "1_1") (pintype "input"))
      (node (ref "U16") (pin "18") (pinfunction "IO4_18") (pintype "unspecified"))
      (node (ref "U5") (pin "3") (pinfunction "SCL_3") (pintype "unspecified"))
    )
    (net (code "9") (name "I2C_SDA") (class "Default")
      (node (ref "F3") (pin "2") (pinfunction "2_2") (pintype "input"))
      (node (ref "U16") (pin "19") (pinfunction "IO5_19") (pintype "unspecified"))
      (node (ref "U5") (pin "4") (pinfunction "SDA_4") (pintype "unspecified"))
    )
    (net (code "10") (name "INT_RTC") (class "Default")
      (node (ref "Q3") (pin "1") (pinfunction "G_1") (pintype "unspecified"))
      (node (ref "R11") (pin "2") (pinfunction "2_2") (pintype "input"))
      (node (ref "U5") (pin "2") (pinfunction "INT#_2") (pintype "unspecified"))
    )
    (net (code "11") (name "KEEP_ALIVE") (class "Default")
      (node (ref "C10") (pin "2") (pinfunction "2_2") (pintype "unspecified"))
      (node (ref "C12") (pin "2") (pinfunction "2_2") (pintype "unspecified"))
      (node (ref "C13") (pin "2") (pinfunction "2_2") (pintype "unspecified"))
      (node (ref "C9") (pin "2") (pinfunction "2_2") (pintype "unspecified"))
      (node (ref "F2") (pin "3") (pinfunction "3_3") (pintype "input"))
      (node (ref "F2") (pin "4") (pinfunction "4_4") (pintype "input"))
      (node (ref "R11") (pin "1") (pinfunction "1_1") (pintype "input"))
      (node (ref "U5") (pin "7") (pinfunction "VDD_7") (pintype "unspecified"))
      (node (ref "U8") (pin "2") (pinfunction "OUT_2") (pintype "unspecified"))
    )
    (net (code "12") (name "MCU_RX_E") (class "Default")
      (node (ref "R48") (pin "1") (pinfunction "1_1") (pintype "input"))
      (node (ref "R49") (pin "2") (pinfunction "2_2") (pintype "input"))
      (node (ref "RN2") (pin "3") (pinfunction "3_3") (pintype "input"))
      (node (ref "U14") (pin "7") (pinfunction "COL/OUT_7") (pintype "unspecified"))
    )
    (net (code "13") (name "MCU_RX_N") (class "Default")
      (node (ref "R38") (pin "1") (pinfunction "1_1") (pintype "input"))
      (node (ref "R39") (pin "2") (pinfunction "2_2") (pintype "input"))
      (node (ref "RN2") (pin "1") (pinfunction "1_1") (pintype "input"))
      (node (ref "U12") (pin "7") (pinfunction "COL/OUT_7") (pintype "unspecified"))
    )
    (net (code "14") (name "MCU_RX_S") (class "Default")
      (node (ref "R43") (pin "1") (pinfunction "1_1") (pintype "input"))
      (node (ref "R44") (pin "2") (pinfunction "2_2") (pintype "input"))
      (node (ref "RN2") (pin "2") (pinfunction "2_2") (pintype "input"))
      (node (ref "U13") (pin "7") (pinfunction "COL/OUT_7") (pintype "unspecified"))
    )
    (net (code "15") (name "MCU_RX_W") (class "Default")
      (node (ref "R53") (pin "1") (pinfunction "1_1") (pintype "input"))
      (node (ref "R54") (pin "2") (pinfunction "2_2") (pintype "input"))
      (node (ref "RN2") (pin "4") (pinfunction "4_4") (pintype "input"))
      (node (ref "U15") (pin "7") (pinfunction "COL/OUT_7") (pintype "unspecified"))
    )
    (net (code "16") (name "Net-(C36-Pad2)") (class "Default")
      (node (ref "C36") (pin "2") (pinfunction "2_2") (pintype "input"))
      (node (ref "R20") (pin "1") (pinfunction "1_1") (pintype "input"))
    )
    (net (code "17") (name "Net-(C39-Pad2)") (class "Default")
      (node (ref "C39") (pin "2") (pinfunction "2_2") (pintype "input"))
      (node (ref "R24") (pin "1") (pinfunction "1_1") (pintype "input"))
    )
    (net (code "18") (name "Net-(C42-Pad2)") (class "Default")
      (node (ref "C42") (pin "2") (pinfunction "2_2") (pintype "input"))
      (node (ref "R28") (pin "1") (pinfunction "1_1") (pintype "input"))
    )
    (net (code "19") (name "Net-(C45-Pad2)") (class "Default")
      (node (ref "C45") (pin "2") (pinfunction "2_2") (pintype "input"))
      (node (ref "R32") (pin "1") (pinfunction "1_1") (pintype "input"))
    )
    (net (code "20") (name "Net-(CN2-Pad1)") (class "Default")
      (node (ref "CN2") (pin "1") (pinfunction "1_1") (pintype "unspecified"))
      (node (ref "F1") (pin "1") (pinfunction "1_1") (pintype "unspecified"))
    )
    (net (code "21") (name "Net-(D3-A)") (class "Default")
      (node (ref "D3") (pin "2") (pinfunction "A_2") (pintype "unspecified"))
      (node (ref "L1") (pin "1") (pinfunction "1_1") (pintype "input"))
      (node (ref "U2") (pin "1") (pinfunction "SW_1") (pintype "unspecified"))
    )
    (net (code "22") (name "Net-(D4-A)") (class "Default")
      (node (ref "D4") (pin "2") (pinfunction "A_2") (pintype "unspecified"))
      (node (ref "L2") (pin "1") (pinfunction "1_1") (pintype "input"))
      (node (ref "U9") (pin "1") (pinfunction "SW_1") (pintype "unspecified"))
    )
    (net (code "23") (name "Net-(LED1-A)") (class "Default")
      (node (ref "LED1") (pin "2") (pinfunction "A_2") (pintype "unspecified"))
      (node (ref "R5") (pin "2") (pinfunction "2_2") (pintype "input"))
    )
    (net (code "24") (name "Net-(LED1-K)") (class "Default")
      (node (ref "C4") (pin "2") (pinfunction "2_2") (pintype "unspecified"))
      (node (ref "C6") (pin "2") (pinfunction "2_2") (pintype "unspecified"))
      (node (ref "LED1") (pin "1") (pinfunction "K_1") (pintype "unspecified"))
      (node (ref "LED2") (pin "1") (pinfunction "K_1") (pintype "unspecified"))
      (node (ref "U4") (pin "5") (pinfunction "BAT_5") (pintype "unspecified"))
      (node (ref "U4") (pin "8") (pinfunction "FB_8") (pintype "unspecified"))
      (node (ref "U6") (pin "1") (pinfunction "1_1") (pintype "unspecified"))
    )
    (net (code "25") (name "Net-(LED2-A)") (class "Default")
      (node (ref "LED2") (pin "2") (pinfunction "A_2") (pintype "unspecified"))
      (node (ref "R4") (pin "2") (pinfunction "2_2") (pintype "input"))
    )
    (net (code "26") (name "Net-(Q1-D)") (class "Default")
      (node (ref "Q1") (pin "3") (pinfunction "D_3") (pintype "unspecified"))
      (node (ref "U7") (pin "1") (pinfunction "1_1") (pintype "unspecified"))
    )
    (net (code "27") (name "Net-(Q1-S)") (class "Default")
      (node (ref "CN1") (pin "1") (pinfunction "1_1") (pintype "unspecified"))
      (node (ref "Q1") (pin "2") (pinfunction "S_2") (pintype "unspecified"))
    )
    (net (code "28") (name "Net-(Q3-D)") (class "Default")
      (node (ref "Q3") (pin "3") (pinfunction "D_3") (pintype "unspecified"))
      (node (ref "Q4") (pin "3") (pinfunction "D_3") (pintype "unspecified"))
      (node (ref "R12") (pin "1") (pinfunction "1_1") (pintype "input"))
    )
    (net (code "29") (name "Net-(Q5-G)") (class "Default")
      (node (ref "Q5") (pin "1") (pinfunction "G_1") (pintype "unspecified"))
      (node (ref "R17") (pin "2") (pinfunction "2_2") (pintype "input"))
    )
    (net (code "30") (name "Net-(Q6-G)") (class "Default")
      (node (ref "Q6") (pin "1") (pinfunction "G_1") (pintype "unspecified"))
      (node (ref "R21") (pin "2") (pinfunction "2_2") (pintype "input"))
    )
    (net (code "31") (name "Net-(Q7-G)") (class "Default")
      (node (ref "Q7") (pin "1") (pinfunction "G_1") (pintype "unspecified"))
      (node (ref "R25") (pin "2") (pinfunction "2_2") (pintype "input"))
    )
    (net (code "32") (name "Net-(Q8-G)") (class "Default")
      (node (ref "Q8") (pin "1") (pinfunction "G_1") (pintype "unspecified"))
      (node (ref "R29") (pin "2") (pinfunction "2_2") (pintype "input"))
    )
    (net (code "33") (name "Net-(U2-FB)") (class "Default")
      (node (ref "R13") (pin "2") (pinfunction "2_2") (pintype "input"))
      (node (ref "R14") (pin "1") (pinfunction "1_1") (pintype "unspecified"))
      (node (ref "U2") (pin "3") (pinfunction "FB_3") (pintype "unspecified"))
    )
    (net (code "34") (name "Net-(U4-ISET)") (class "Default")
      (node (ref "R2") (pin "2") (pinfunction "2_2") (pintype "input"))
      (node (ref "U4") (pin "2") (pinfunction "ISET_2") (pintype "unspecified"))
    )
    (net (code "35") (name "Net-(U4-TEMP)") (class "Default")
      (node (ref "R3") (pin "2") (pinfunction "2_2") (pintype "input"))
      (node (ref "U4") (pin "1") (pinfunction "TEMP_1") (pintype "unspecified"))
    )
    (net (code "36") (name "Net-(U4-VIN)") (class "Default")
      (node (ref "C3") (pin "2") (pinfunction "2_2") (pintype "unspecified"))
      (node (ref "C5") (pin "2") (pinfunction "2_2") (pintype "unspecified"))
      (node (ref "F1") (pin "2") (pinfunction "2_2") (pintype "unspecified"))
      (node (ref "U4") (pin "4") (pinfunction "VIN_4") (pintype "unspecified"))
    )
    (net (code "37") (name "Net-(U5-EVI)") (class "Default")
      (node (ref "R6") (pin "1") (pinfunction "1_1") (pintype "input"))
      (node (ref "U5") (pin "8") (pinfunction "EVI_8") (pintype "unspecified"))
    )
    (net (code "38") (name "Net-(U5-VBACKUP)") (class "Default")
      (node (ref "C11") (pin "2") (pinfunction "2_2") (pintype "unspecified"))
      (node (ref "R9") (pin "1") (pinfunction "1_1") (pintype "input"))
      (node (ref "U5") (pin "6") (pinfunction "VBACKUP_6") (pintype "unspecified"))
    )
    (net (code "39") (name "Net-(U9-FB)") (class "Default")
      (node (ref "R15") (pin "1") (pinfunction "1_1") (pintype "input"))
      (node (ref "R16") (pin "2") (pinfunction "2_2") (pintype "input"))
      (node (ref "U9") (pin "3") (pinfunction "FB_3") (pintype "unspecified"))
    )
    (net (code "40") (name "Net-(U10A-INA+)") (class "Default")
      (node (ref "C48") (pin "2") (pinfunction "2_2") (pintype "input"))
      (node (ref "R35") (pin "2") (pinfunction "2_2") (pintype "input"))
      (node (ref "U10") (pin "3") (pinfunction "INA+_3") (pintype "unspecified"))
    )
    (net (code "41") (name "Net-(U10A-INA-)") (class "Default")
      (node (ref "R36") (pin "2") (pinfunction "2_2") (pintype "input"))
      (node (ref "R37") (pin "2") (pinfunction "2_2") (pintype "input"))
      (node (ref "U10") (pin "2") (pinfunction "INA-_2") (pintype "unspecified"))
    )
    (net (code "42") (name "Net-(U10B-INB+)") (class "Default")
      (node (ref "C51") (pin "2") (pinfunction "2_2") (pintype "input"))
      (node (ref "R40") (pin "2") (pinfunction "2_2") (pintype "input"))
      (node (ref "U10") (pin "5") (pinfunction "INB+_5") (pintype "unspecified"))
    )
    (net (code "43") (name "Net-(U10B-INB-)") (class "Default")
      (node (ref "R41") (pin "2") (pinfunction "2_2") (pintype "input"))
      (node (ref "R42") (pin "2") (pinfunction "2_2") (pintype "input"))
      (node (ref "U10") (pin "6") (pinfunction "INB-_6") (pintype "unspecified"))
    )
    (net (code "44") (name "Net-(U11A-INA+)") (class "Default")
      (node (ref "C54") (pin "2") (pinfunction "2_2") (pintype "input"))
      (node (ref "R45") (pin "2") (pinfunction "2_2") (pintype "input"))
      (node (ref "U11") (pin "3") (pinfunction "INA+_3") (pintype "unspecified"))
    )
    (net (code "45") (name "Net-(U11A-INA-)") (class "Default")
      (node (ref "R46") (pin "2") (pinfunction "2_2") (pintype "input"))
      (node (ref "R47") (pin "2") (pinfunction "2_2") (pintype "input"))
      (node (ref "U11") (pin "2") (pinfunction "INA-_2") (pintype "unspecified"))
    )
    (net (code "46") (name "Net-(U11B-INB+)") (class "Default")
      (node (ref "C57") (pin "2") (pinfunction "2_2") (pintype "input"))
      (node (ref "R50") (pin "2") (pinfunction "2_2") (pintype "input"))
      (node (ref "U11") (pin "5") (pinfunction "INB+_5") (pintype "unspecified"))
    )
    (net (code "47") (name "Net-(U11B-INB-)") (class "Default")
      (node (ref "R51") (pin "2") (pinfunction "2_2") (pintype "input"))
      (node (ref "R52") (pin "2") (pinfunction "2_2") (pintype "input"))
      (node (ref "U11") (pin "6") (pinfunction "INB-_6") (pintype "unspecified"))
    )
    (net (code "48") (name "Net-(U16-IO2)") (class "Default")
      (node (ref "R57") (pin "2") (pinfunction "2_2") (pintype "input"))
      (node (ref "U16") (pin "5") (pinfunction "IO2_5") (pintype "unspecified"))
    )
    (net (code "49") (name "PROG_BOOT") (class "Default")
      (node (ref "R56") (pin "2") (pinfunction "2_2") (pintype "input"))
      (node (ref "SW3") (pin "2") (pinfunction "2_2") (pintype "unspecified"))
      (node (ref "U16") (pin "23") (pinfunction "IO9_23") (pintype "unspecified"))
      (node (ref "U17") (pin "6") (pinfunction "6_6") (pintype "unspecified"))
    )
    (net (code "50") (name "PROG_EN") (class "Default")
      (node (ref "C62") (pin "2") (pinfunction "2_2") (pintype "unspecified"))
      (node (ref "R55") (pin "2") (pinfunction "2_2") (pintype "input"))
      (node (ref "SW2") (pin "2") (pinfunction "2_2") (pintype "unspecified"))
      (node (ref "U16") (pin "8") (pinfunction "EN_8") (pintype "unspecified"))
      (node (ref "U17") (pin "5") (pinfunction "5_5") (pintype "unspecified"))
    )
    (net (code "51") (name "PWR_HOLD") (class "Default")
      (node (ref "Q4") (pin "1") (pinfunction "G_1") (pintype "unspecified"))
      (node (ref "R59") (pin "2") (pinfunction "2_2") (pintype "input"))
      (node (ref "R60") (pin "2") (pinfunction "2_2") (pintype "input"))
      (node (ref "U16") (pin "22") (pinfunction "IO8_22") (pintype "unspecified"))
    )
    (net (code "52") (name "RAW_BAT") (class "Default")
      (node (ref "C14") (pin "2") (pinfunction "2_2") (pintype "unspecified"))
      (node (ref "C7") (pin "2") (pinfunction "2_2") (pintype "unspecified"))
      (node (ref "C8") (pin "2") (pinfunction "2_2") (pintype "unspecified"))
      (node (ref "D1") (pin "2") (pinfunction "K_2") (pintype "input"))
      (node (ref "Q2") (pin "2") (pinfunction "S_2") (pintype "unspecified"))
      (node (ref "R10") (pin "2") (pinfunction "2_2") (pintype "input"))
      (node (ref "U6") (pin "2") (pinfunction "2_2") (pintype "unspecified"))
      (node (ref "U7") (pin "2") (pinfunction "2_2") (pintype "unspecified"))
      (node (ref "U8") (pin "3") (pinfunction "IN_3") (pintype "unspecified"))
    )
    (net (code "53") (name "RX") (class "Default")
      (node (ref "U16") (pin "30") (pinfunction "RXD0_30") (pintype "unspecified"))
      (node (ref "U17") (pin "4") (pinfunction "4_4") (pintype "unspecified"))
    )
    (net (code "54") (name "RX_OP_E") (class "Default")
      (node (ref "R46") (pin "1") (pinfunction "1_1") (pintype "input"))
      (node (ref "R49") (pin "1") (pinfunction "1_1") (pintype "input"))
      (node (ref "U11") (pin "1") (pinfunction "OUTA_1") (pintype "output"))
      (node (ref "U14") (pin "2") (pinfunction "IN+_2") (pintype "unspecified"))
    )
    (net (code "55") (name "RX_OP_N") (class "Default")
      (node (ref "R36") (pin "1") (pinfunction "1_1") (pintype "input"))
      (node (ref "R39") (pin "1") (pinfunction "1_1") (pintype "input"))
      (node (ref "U10") (pin "1") (pinfunction "OUTA_1") (pintype "output"))
      (node (ref "U12") (pin "2") (pinfunction "IN+_2") (pintype "unspecified"))
    )
    (net (code "56") (name "RX_OP_S") (class "Default")
      (node (ref "R41") (pin "1") (pinfunction "1_1") (pintype "input"))
      (node (ref "R44") (pin "1") (pinfunction "1_1") (pintype "input"))
      (node (ref "U10") (pin "7") (pinfunction "OUTB_7") (pintype "output"))
      (node (ref "U13") (pin "2") (pinfunction "IN+_2") (pintype "unspecified"))
    )
    (net (code "57") (name "RX_OP_W") (class "Default")
      (node (ref "R51") (pin "1") (pinfunction "1_1") (pintype "input"))
      (node (ref "R54") (pin "1") (pinfunction "1_1") (pintype "input"))
      (node (ref "U11") (pin "7") (pinfunction "OUTB_7") (pintype "output"))
      (node (ref "U15") (pin "2") (pinfunction "IN+_2") (pintype "unspecified"))
    )
    (net (code "58") (name "R_RX_E") (class "Default")
      (node (ref "RN2") (pin "6") (pinfunction "6_6") (pintype "input"))
      (node (ref "U16") (pin "26") (pinfunction "IO18_26") (pintype "unspecified"))
    )
    (net (code "59") (name "R_RX_N") (class "Default")
      (node (ref "RN2") (pin "8") (pinfunction "8_8") (pintype "input"))
      (node (ref "U16") (pin "21") (pinfunction "IO7_21") (pintype "unspecified"))
    )
    (net (code "60") (name "R_RX_S") (class "Default")
      (node (ref "RN2") (pin "7") (pinfunction "7_7") (pintype "input"))
      (node (ref "U16") (pin "16") (pinfunction "IO10_16") (pintype "unspecified"))
    )
    (net (code "61") (name "R_RX_W") (class "Default")
      (node (ref "RN2") (pin "5") (pinfunction "5_5") (pintype "input"))
      (node (ref "U16") (pin "27") (pinfunction "IO19_27") (pintype "unspecified"))
    )
    (net (code "62") (name "R_TX_E") (class "Default")
      (node (ref "RN1") (pin "6") (pinfunction "6_6") (pintype "input"))
      (node (ref "U16") (pin "6") (pinfunction "IO3_6") (pintype "unspecified"))
    )
    (net (code "63") (name "R_TX_N") (class "Default")
      (node (ref "RN1") (pin "8") (pinfunction "8_8") (pintype "input"))
      (node (ref "U16") (pin "12") (pinfunction "IO0_12") (pintype "unspecified"))
    )
    (net (code "64") (name "R_TX_S") (class "Default")
      (node (ref "RN1") (pin "7") (pinfunction "7_7") (pintype "input"))
      (node (ref "U16") (pin "13") (pinfunction "IO1_13") (pintype "unspecified"))
    )
    (net (code "65") (name "R_TX_W") (class "Default")
      (node (ref "RN1") (pin "5") (pinfunction "5_5") (pintype "input"))
      (node (ref "U16") (pin "20") (pinfunction "IO6_20") (pintype "unspecified"))
    )
    (net (code "66") (name "SCL") (class "Default")
      (node (ref "F2") (pin "1") (pinfunction "1_1") (pintype "input"))
    )
    (net (code "67") (name "SDA") (class "Default")
      (node (ref "F2") (pin "2") (pinfunction "2_2") (pintype "input"))
    )
    (net (code "68") (name "SYS_GATE") (class "Default")
      (node (ref "C14") (pin "1") (pinfunction "1_1") (pintype "unspecified"))
      (node (ref "Q2") (pin "1") (pinfunction "G_1") (pintype "unspecified"))
      (node (ref "R10") (pin "1") (pinfunction "1_1") (pintype "input"))
      (node (ref "R12") (pin "2") (pinfunction "2_2") (pintype "input"))
      (node (ref "SW1") (pin "1") (pinfunction "1_1") (pintype "unspecified"))
    )
    (net (code "69") (name "TX") (class "Default")
      (node (ref "U16") (pin "31") (pinfunction "TXD0_31") (pintype "unspecified"))
      (node (ref "U17") (pin "3") (pinfunction "3_3") (pintype "unspecified"))
    )
    (net (code "70") (name "TX_PULSE_E") (class "Default")
      (node (ref "R29") (pin "1") (pinfunction "1_1") (pintype "input"))
      (node (ref "R30") (pin "1") (pinfunction "1_1") (pintype "input"))
      (node (ref "RN1") (pin "3") (pinfunction "3_3") (pintype "input"))
    )
    (net (code "71") (name "TX_PULSE_N") (class "Default")
      (node (ref "R17") (pin "1") (pinfunction "1_1") (pintype "input"))
      (node (ref "R18") (pin "1") (pinfunction "1_1") (pintype "input"))
      (node (ref "RN1") (pin "1") (pinfunction "1_1") (pintype "input"))
    )
    (net (code "72") (name "TX_PULSE_S") (class "Default")
      (node (ref "R21") (pin "1") (pinfunction "1_1") (pintype "input"))
      (node (ref "R22") (pin "1") (pinfunction "1_1") (pintype "input"))
      (node (ref "RN1") (pin "2") (pinfunction "2_2") (pintype "input"))
    )
    (net (code "73") (name "TX_PULSE_W") (class "Default")
      (node (ref "R25") (pin "1") (pinfunction "1_1") (pintype "input"))
      (node (ref "R26") (pin "1") (pinfunction "1_1") (pintype "input"))
      (node (ref "RN1") (pin "4") (pinfunction "4_4") (pintype "input"))
    )
    (net (code "74") (name "VBU") (class "Default")
      (node (ref "B1") (pin "1") (pinfunction "1_1") (pintype "input"))
      (node (ref "R9") (pin "2") (pinfunction "2_2") (pintype "input"))
    )
    (net (code "75") (name "VSYS") (class "Default")
      (node (ref "C15") (pin "2") (pinfunction "2_2") (pintype "unspecified"))
      (node (ref "C16") (pin "2") (pinfunction "2_2") (pintype "unspecified"))
      (node (ref "C21") (pin "2") (pinfunction "2_2") (pintype "unspecified"))
      (node (ref "C24") (pin "2") (pinfunction "2_2") (pintype "unspecified"))
      (node (ref "C30") (pin "2") (pinfunction "2_2") (pintype "unspecified"))
      (node (ref "C32") (pin "2") (pinfunction "2_2") (pintype "unspecified"))
      (node (ref "L1") (pin "2") (pinfunction "2_2") (pintype "input"))
      (node (ref "L2") (pin "2") (pinfunction "2_2") (pintype "input"))
      (node (ref "Q2") (pin "3") (pinfunction "D_3") (pintype "unspecified"))
      (node (ref "U1") (pin "1") (pinfunction "VIN_1") (pintype "unspecified"))
      (node (ref "U1") (pin "3") (pinfunction "EN_3") (pintype "unspecified"))
      (node (ref "U2") (pin "4") (pinfunction "EN_4") (pintype "unspecified"))
      (node (ref "U2") (pin "5") (pinfunction "IN_5") (pintype "unspecified"))
      (node (ref "U9") (pin "4") (pinfunction "EN_4") (pintype "unspecified"))
      (node (ref "U9") (pin "5") (pinfunction "IN_5") (pintype "unspecified"))
    )
    (net (code "76") (name "XDUC_E+") (class "Default")
      (node (ref "C54") (pin "1") (pinfunction "1_1") (pintype "input"))
      (node (ref "CN6") (pin "1") (pinfunction "1_1") (pintype "unspecified"))
      (node (ref "R31") (pin "2") (pinfunction "2_2") (pintype "input"))
    )
    (net (code "77") (name "XDUC_E-") (class "Default")
      (node (ref "CN6") (pin "2") (pinfunction "2_2") (pintype "unspecified"))
      (node (ref "Q8") (pin "3") (pinfunction "D_3") (pintype "unspecified"))
      (node (ref "R32") (pin "2") (pinfunction "2_2") (pintype "input"))
    )
    (net (code "78") (name "XDUC_N+") (class "Default")
      (node (ref "C48") (pin "1") (pinfunction "1_1") (pintype "input"))
      (node (ref "CN3") (pin "1") (pinfunction "1_1") (pintype "unspecified"))
      (node (ref "R19") (pin "2") (pinfunction "2_2") (pintype "input"))
    )
    (net (code "79") (name "XDUC_N-") (class "Default")
      (node (ref "CN3") (pin "2") (pinfunction "2_2") (pintype "unspecified"))
      (node (ref "Q5") (pin "3") (pinfunction "D_3") (pintype "unspecified"))
      (node (ref "R20") (pin "2") (pinfunction "2_2") (pintype "input"))
    )
    (net (code "80") (name "XDUC_S+") (class "Default")
      (node (ref "C51") (pin "1") (pinfunction "1_1") (pintype "input"))
      (node (ref "CN4") (pin "1") (pinfunction "1_1") (pintype "unspecified"))
      (node (ref "R23") (pin "2") (pinfunction "2_2") (pintype "input"))
    )
    (net (code "81") (name "XDUC_S-") (class "Default")
      (node (ref "CN4") (pin "2") (pinfunction "2_2") (pintype "unspecified"))
      (node (ref "Q6") (pin "3") (pinfunction "D_3") (pintype "unspecified"))
      (node (ref "R24") (pin "2") (pinfunction "2_2") (pintype "input"))
    )
    (net (code "82") (name "XDUC_W+") (class "Default")
      (node (ref "C57") (pin "1") (pinfunction "1_1") (pintype "input"))
      (node (ref "CN5") (pin "1") (pinfunction "1_1") (pintype "unspecified"))
      (node (ref "R27") (pin "2") (pinfunction "2_2") (pintype "input"))
    )
    (net (code "83") (name "XDUC_W-") (class "Default")
      (node (ref "CN5") (pin "2") (pinfunction "2_2") (pintype "unspecified"))
      (node (ref "Q7") (pin "3") (pinfunction "D_3") (pintype "unspecified"))
      (node (ref "R28") (pin "2") (pinfunction "2_2") (pintype "input"))
    )
    (net (code "84") (name "unconnected-(CN1-Pad3)") (class "Default")
      (node (ref "CN1") (pin "3") (pinfunction "3_3") (pintype "unspecified"))
    )
    (net (code "85") (name "unconnected-(CN1-Pad4)") (class "Default")
      (node (ref "CN1") (pin "4") (pinfunction "4_4") (pintype "unspecified"))
    )
    (net (code "86") (name "unconnected-(CN2-Pad3)") (class "Default")
      (node (ref "CN2") (pin "3") (pinfunction "3_3") (pintype "unspecified"))
    )
    (net (code "87") (name "unconnected-(CN2-Pad4)") (class "Default")
      (node (ref "CN2") (pin "4") (pinfunction "4_4") (pintype "unspecified"))
    )
    (net (code "88") (name "unconnected-(CN3-Pad3)") (class "Default")
      (node (ref "CN3") (pin "3") (pinfunction "3_3") (pintype "unspecified"))
    )
    (net (code "89") (name "unconnected-(CN3-Pad4)") (class "Default")
      (node (ref "CN3") (pin "4") (pinfunction "4_4") (pintype "unspecified"))
    )
    (net (code "90") (name "unconnected-(CN4-Pad3)") (class "Default")
      (node (ref "CN4") (pin "3") (pinfunction "3_3") (pintype "unspecified"))
    )
    (net (code "91") (name "unconnected-(CN4-Pad4)") (class "Default")
      (node (ref "CN4") (pin "4") (pinfunction "4_4") (pintype "unspecified"))
    )
    (net (code "92") (name "unconnected-(CN5-Pad3)") (class "Default")
      (node (ref "CN5") (pin "3") (pinfunction "3_3") (pintype "unspecified"))
    )
    (net (code "93") (name "unconnected-(CN5-Pad4)") (class "Default")
      (node (ref "CN5") (pin "4") (pinfunction "4_4") (pintype "unspecified"))
    )
    (net (code "94") (name "unconnected-(CN6-Pad3)") (class "Default")
      (node (ref "CN6") (pin "3") (pinfunction "3_3") (pintype "unspecified"))
    )
    (net (code "95") (name "unconnected-(CN6-Pad4)") (class "Default")
      (node (ref "CN6") (pin "4") (pinfunction "4_4") (pintype "unspecified"))
    )
    (net (code "96") (name "unconnected-(U1-NC-Pad4)") (class "Default")
      (node (ref "U1") (pin "4") (pinfunction "NC_4") (pintype "unspecified+no_connect"))
    )
    (net (code "97") (name "unconnected-(U2-NC-Pad6)") (class "Default")
      (node (ref "U2") (pin "6") (pinfunction "NC_6") (pintype "unspecified+no_connect"))
    )
    (net (code "98") (name "unconnected-(U4-PAD-Pad9)") (class "Default")
      (node (ref "U4") (pin "9") (pinfunction "PAD_9") (pintype "unspecified"))
    )
    (net (code "99") (name "unconnected-(U5-CLKOUT-Pad1)") (class "Default")
      (node (ref "U5") (pin "1") (pinfunction "CLKOUT_1") (pintype "unspecified+no_connect"))
    )
    (net (code "100") (name "unconnected-(U9-NC-Pad6)") (class "Default")
      (node (ref "U9") (pin "6") (pinfunction "NC_6") (pintype "unspecified+no_connect"))
    )
    (net (code "101") (name "unconnected-(U12-BALANCE-Pad5)") (class "Default")
      (node (ref "U12") (pin "5") (pinfunction "BALANCE_5") (pintype "unspecified+no_connect"))
    )
    (net (code "102") (name "unconnected-(U13-BALANCE-Pad5)") (class "Default")
      (node (ref "U13") (pin "5") (pinfunction "BALANCE_5") (pintype "unspecified+no_connect"))
    )
    (net (code "103") (name "unconnected-(U14-BALANCE-Pad5)") (class "Default")
      (node (ref "U14") (pin "5") (pinfunction "BALANCE_5") (pintype "unspecified+no_connect"))
    )
    (net (code "104") (name "unconnected-(U15-BALANCE-Pad5)") (class "Default")
      (node (ref "U15") (pin "5") (pinfunction "BALANCE_5") (pintype "unspecified+no_connect"))
    )
    (net (code "105") (name "unconnected-(U16-GND-Pad1)") (class "Default")
      (node (ref "U16") (pin "1") (pinfunction "GND_1") (pintype "unspecified"))
    )
    (net (code "106") (name "unconnected-(U16-GND-Pad2)") (class "Default")
      (node (ref "U16") (pin "2") (pinfunction "GND_2") (pintype "unspecified"))
    )
    (net (code "107") (name "unconnected-(U16-GND-Pad11)") (class "Default")
      (node (ref "U16") (pin "11") (pinfunction "GND_11") (pintype "unspecified"))
    )
    (net (code "108") (name "unconnected-(U16-GND-Pad14)") (class "Default")
      (node (ref "U16") (pin "14") (pinfunction "GND_14") (pintype "unspecified"))
    )
    (net (code "109") (name "unconnected-(U16-GND-Pad36)") (class "Default")
      (node (ref "U16") (pin "36") (pinfunction "GND_36") (pintype "unspecified"))
    )
    (net (code "110") (name "unconnected-(U16-GND-Pad37)") (class "Default")
      (node (ref "U16") (pin "37") (pinfunction "GND_37") (pintype "unspecified"))
    )
    (net (code "111") (name "unconnected-(U16-GND-Pad38)") (class "Default")
      (node (ref "U16") (pin "38") (pinfunction "GND_38") (pintype "unspecified"))
    )
    (net (code "112") (name "unconnected-(U16-GND-Pad39)") (class "Default")
      (node (ref "U16") (pin "39") (pinfunction "GND_39") (pintype "unspecified"))
    )
    (net (code "113") (name "unconnected-(U16-GND-Pad40)") (class "Default")
      (node (ref "U16") (pin "40") (pinfunction "GND_40") (pintype "unspecified"))
    )
    (net (code "114") (name "unconnected-(U16-GND-Pad41)") (class "Default")
      (node (ref "U16") (pin "41") (pinfunction "GND_41") (pintype "unspecified"))
    )
    (net (code "115") (name "unconnected-(U16-GND-Pad42)") (class "Default")
      (node (ref "U16") (pin "42") (pinfunction "GND_42") (pintype "unspecified"))
    )
    (net (code "116") (name "unconnected-(U16-GND-Pad43)") (class "Default")
      (node (ref "U16") (pin "43") (pinfunction "GND_43") (pintype "unspecified"))
    )
    (net (code "117") (name "unconnected-(U16-GND-Pad44)") (class "Default")
      (node (ref "U16") (pin "44") (pinfunction "GND_44") (pintype "unspecified"))
    )
    (net (code "118") (name "unconnected-(U16-GND-Pad45)") (class "Default")
      (node (ref "U16") (pin "45") (pinfunction "GND_45") (pintype "unspecified"))
    )
    (net (code "119") (name "unconnected-(U16-GND-Pad46)") (class "Default")
      (node (ref "U16") (pin "46") (pinfunction "GND_46") (pintype "unspecified"))
    )
    (net (code "120") (name "unconnected-(U16-GND-Pad47)") (class "Default")
      (node (ref "U16") (pin "47") (pinfunction "GND_47") (pintype "unspecified"))
    )
    (net (code "121") (name "unconnected-(U16-GND-Pad48)") (class "Default")
      (node (ref "U16") (pin "48") (pinfunction "GND_48") (pintype "unspecified"))
    )
    (net (code "122") (name "unconnected-(U16-GND-Pad49)") (class "Default")
      (node (ref "U16") (pin "49") (pinfunction "GND_49") (pintype "unspecified"))
    )
    (net (code "123") (name "unconnected-(U16-GND-Pad50)") (class "Default")
      (node (ref "U16") (pin "50") (pinfunction "GND_50") (pintype "unspecified"))
    )
    (net (code "124") (name "unconnected-(U16-GND-Pad51)") (class "Default")
      (node (ref "U16") (pin "51") (pinfunction "GND_51") (pintype "unspecified"))
    )
    (net (code "125") (name "unconnected-(U16-GND-Pad52)") (class "Default")
      (node (ref "U16") (pin "52") (pinfunction "GND_52") (pintype "unspecified"))
    )
    (net (code "126") (name "unconnected-(U16-GND-Pad53)") (class "Default")
      (node (ref "U16") (pin "53") (pinfunction "GND_53") (pintype "unspecified"))
    )
    (net (code "127") (name "unconnected-(U16-NC-Pad4)") (class "Default")
      (node (ref "U16") (pin "4") (pinfunction "NC_4") (pintype "unspecified"))
    )
    (net (code "128") (name "unconnected-(U16-NC-Pad7)") (class "Default")
      (node (ref "U16") (pin "7") (pinfunction "NC_7") (pintype "unspecified"))
    )
    (net (code "129") (name "unconnected-(U16-NC-Pad9)") (class "Default")
      (node (ref "U16") (pin "9") (pinfunction "NC_9") (pintype "unspecified"))
    )
    (net (code "130") (name "unconnected-(U16-NC-Pad10)") (class "Default")
      (node (ref "U16") (pin "10") (pinfunction "NC_10") (pintype "unspecified"))
    )
    (net (code "131") (name "unconnected-(U16-NC-Pad15)") (class "Default")
      (node (ref "U16") (pin "15") (pinfunction "NC_15") (pintype "unspecified"))
    )
    (net (code "132") (name "unconnected-(U16-NC-Pad17)") (class "Default")
      (node (ref "U16") (pin "17") (pinfunction "NC_17") (pintype "unspecified"))
    )
    (net (code "133") (name "unconnected-(U16-NC-Pad24)") (class "Default")
      (node (ref "U16") (pin "24") (pinfunction "NC_24") (pintype "unspecified"))
    )
    (net (code "134") (name "unconnected-(U16-NC-Pad25)") (class "Default")
      (node (ref "U16") (pin "25") (pinfunction "NC_25") (pintype "unspecified"))
    )
    (net (code "135") (name "unconnected-(U16-NC-Pad28)") (class "Default")
      (node (ref "U16") (pin "28") (pinfunction "NC_28") (pintype "unspecified"))
    )
    (net (code "136") (name "unconnected-(U16-NC-Pad29)") (class "Default")
      (node (ref "U16") (pin "29") (pinfunction "NC_29") (pintype "unspecified"))
    )
    (net (code "137") (name "unconnected-(U16-NC-Pad32)") (class "Default")
      (node (ref "U16") (pin "32") (pinfunction "NC_32") (pintype "unspecified"))
    )
    (net (code "138") (name "unconnected-(U16-NC-Pad33)") (class "Default")
      (node (ref "U16") (pin "33") (pinfunction "NC_33") (pintype "unspecified"))
    )
    (net (code "139") (name "unconnected-(U16-NC-Pad34)") (class "Default")
      (node (ref "U16") (pin "34") (pinfunction "NC_34") (pintype "unspecified"))
    )
    (net (code "140") (name "unconnected-(U16-NC-Pad35)") (class "Default")
      (node (ref "U16") (pin "35") (pinfunction "NC_35") (pintype "unspecified"))
    )
    (net (code "141") (name "unconnected-(U17-Pad7)") (class "Default")
      (node (ref "U17") (pin "7") (pinfunction "7_7") (pintype "unspecified"))
    )
    (net (code "142") (name "unconnected-(U17-Pad8)") (class "Default")
      (node (ref "U17") (pin "8") (pinfunction "8_8") (pintype "unspecified"))
    )
  )
)
